# 5_8GHzRadar.net
KiCad netlist of a schematic drawn in EAGLE
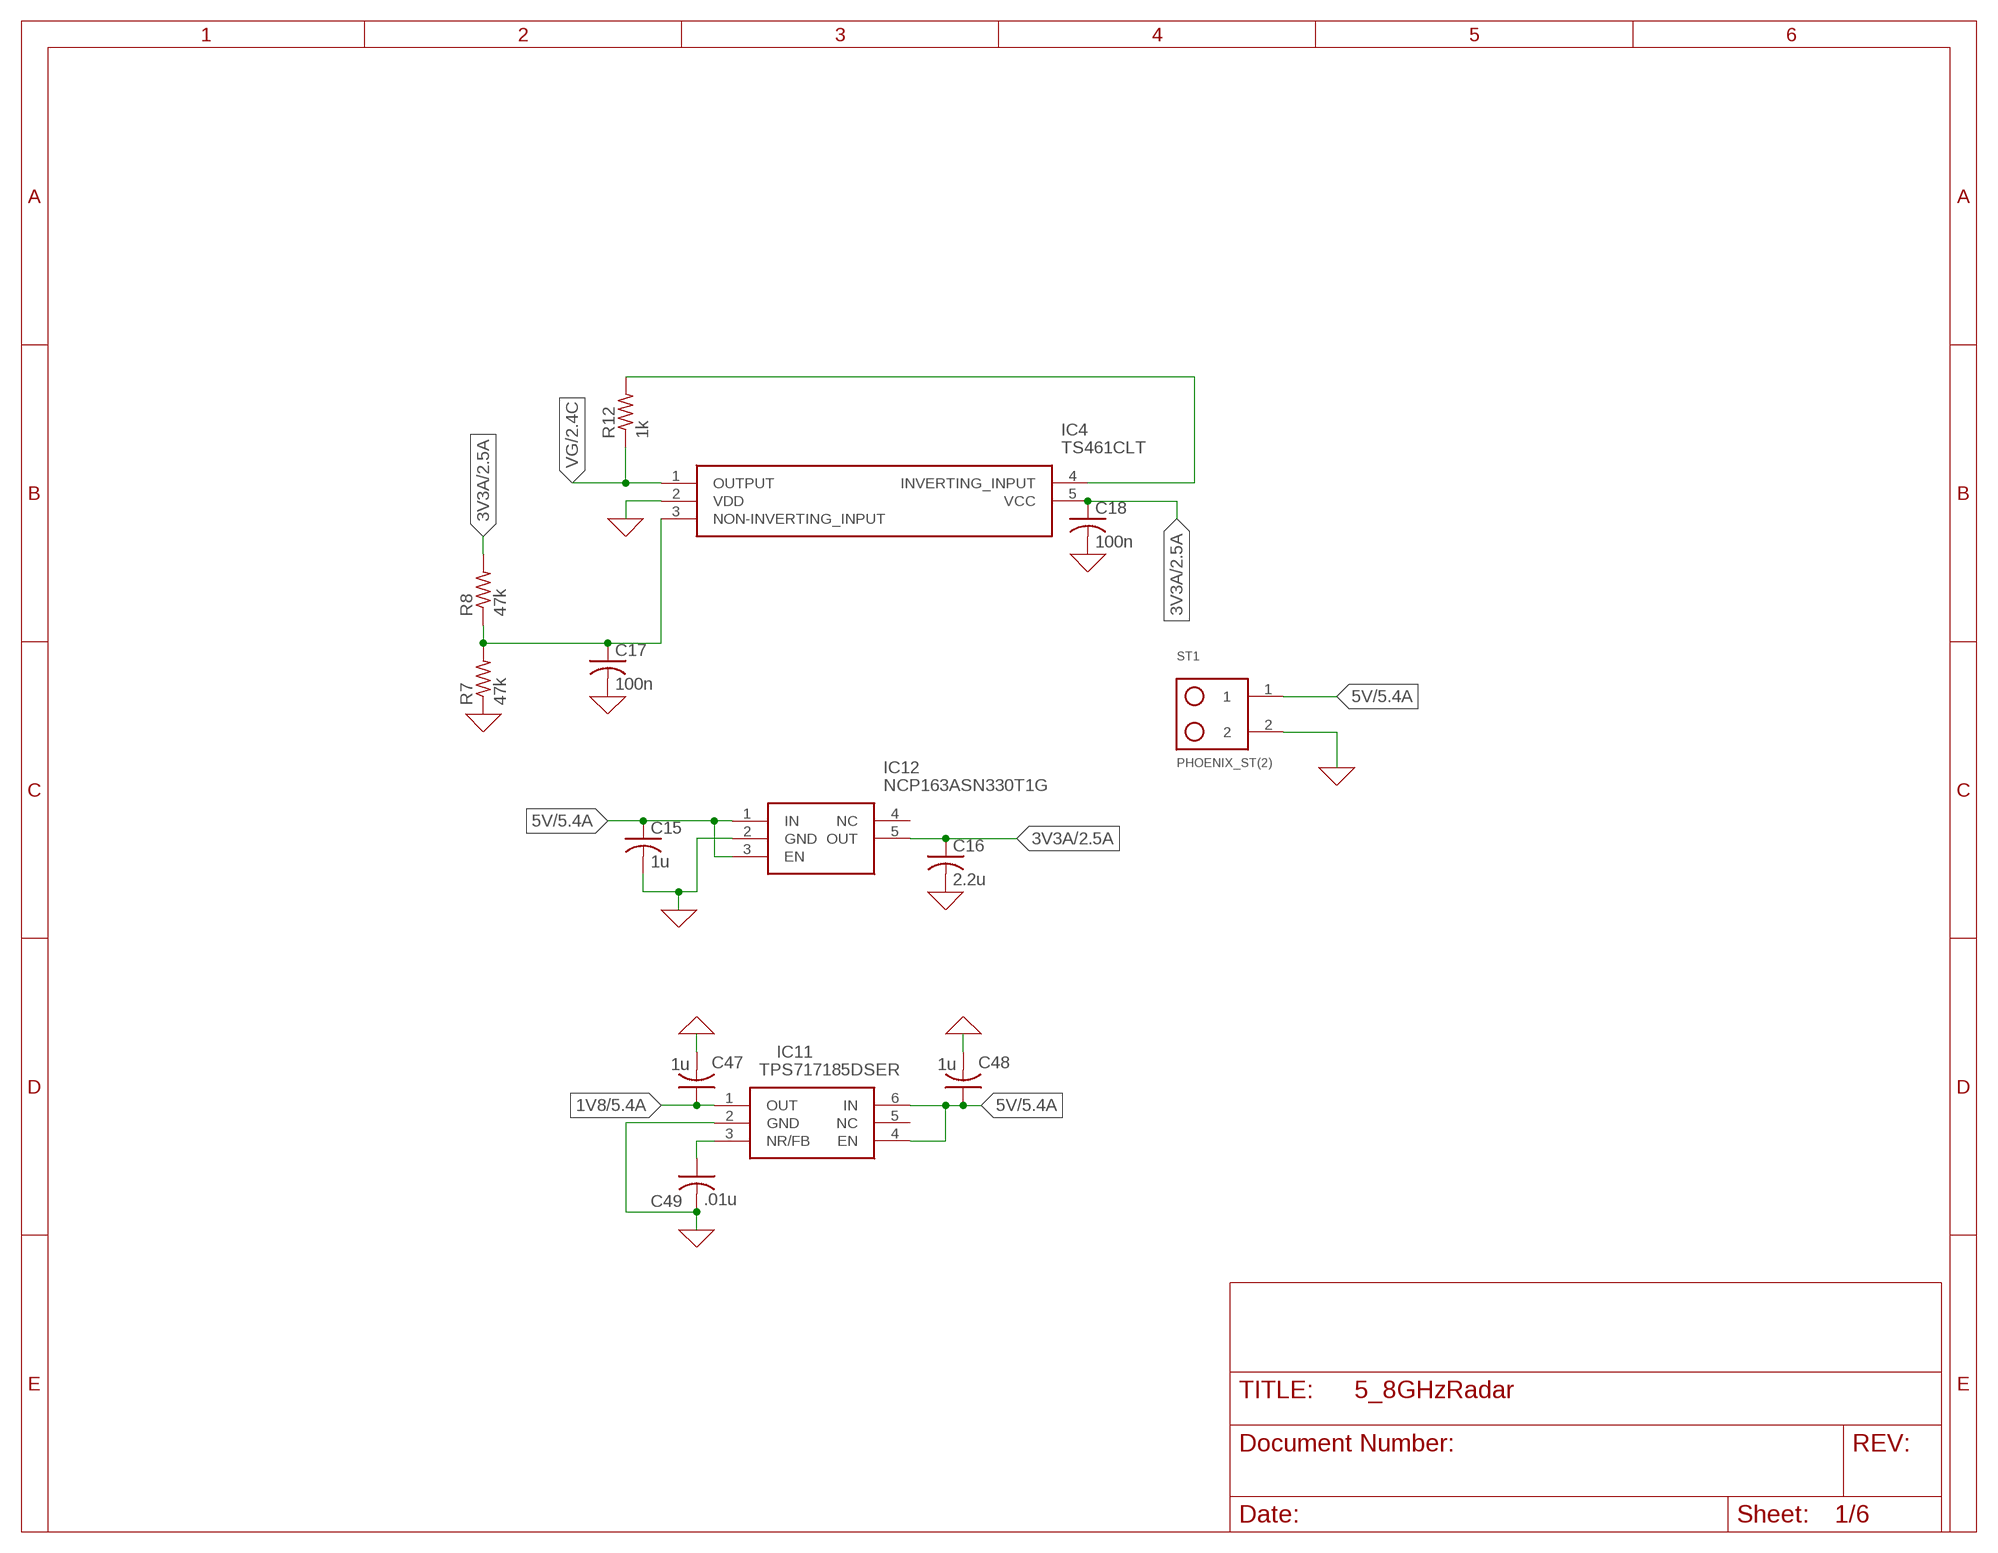
[diagram p0: schematic, sheet 1]
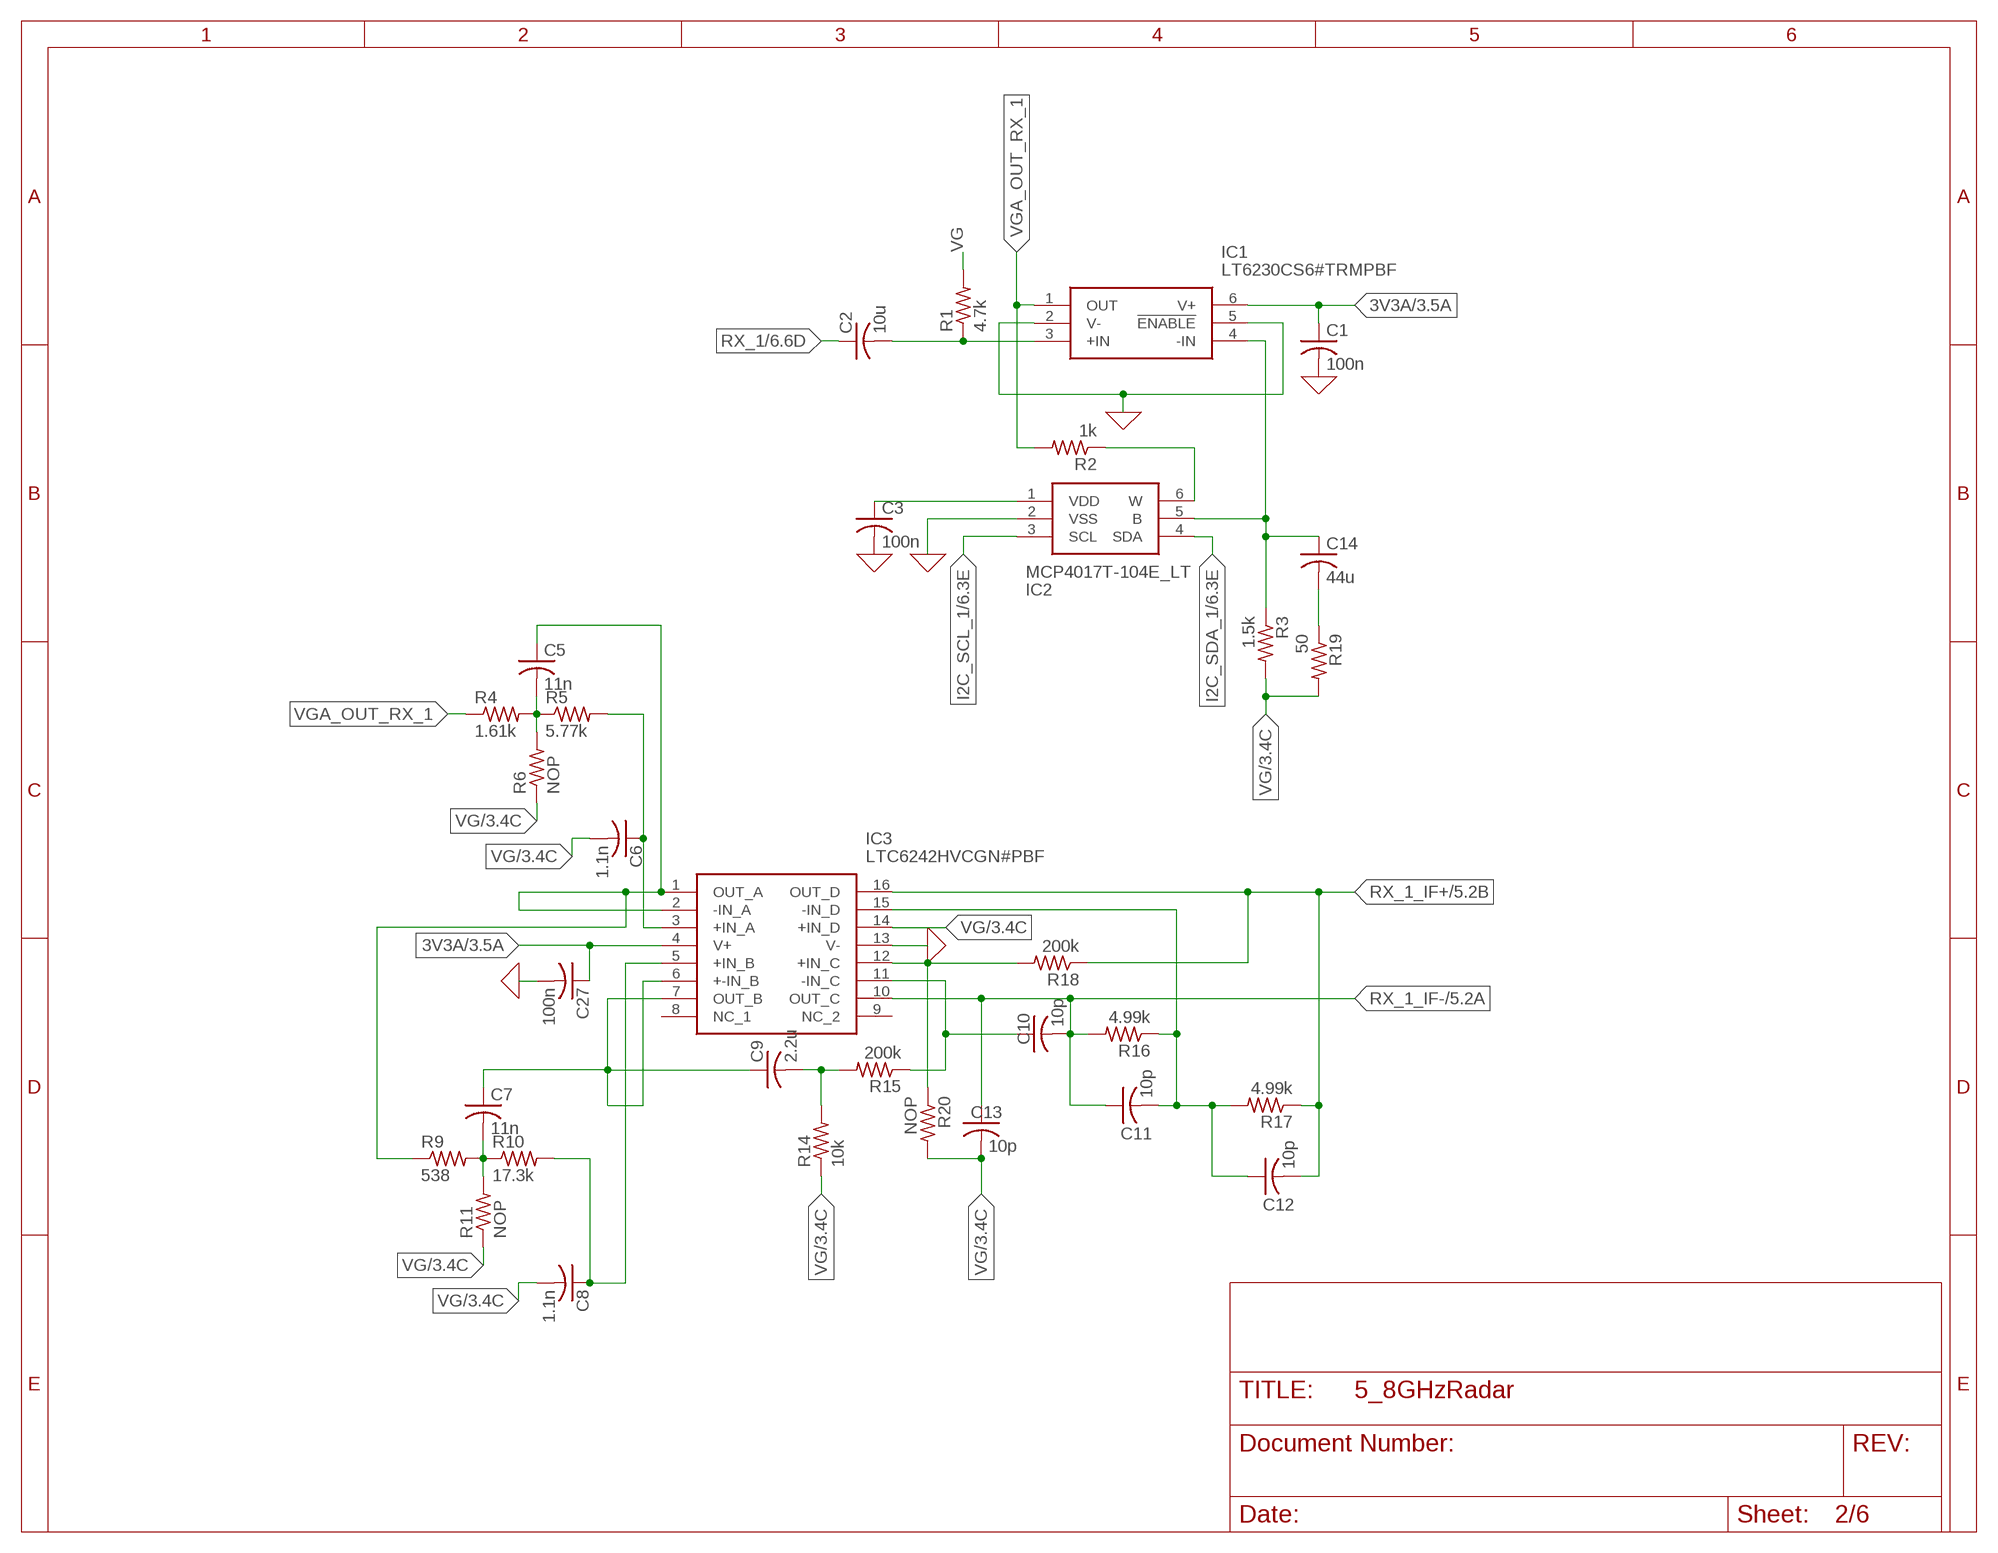
[diagram p1: schematic, sheet 2]
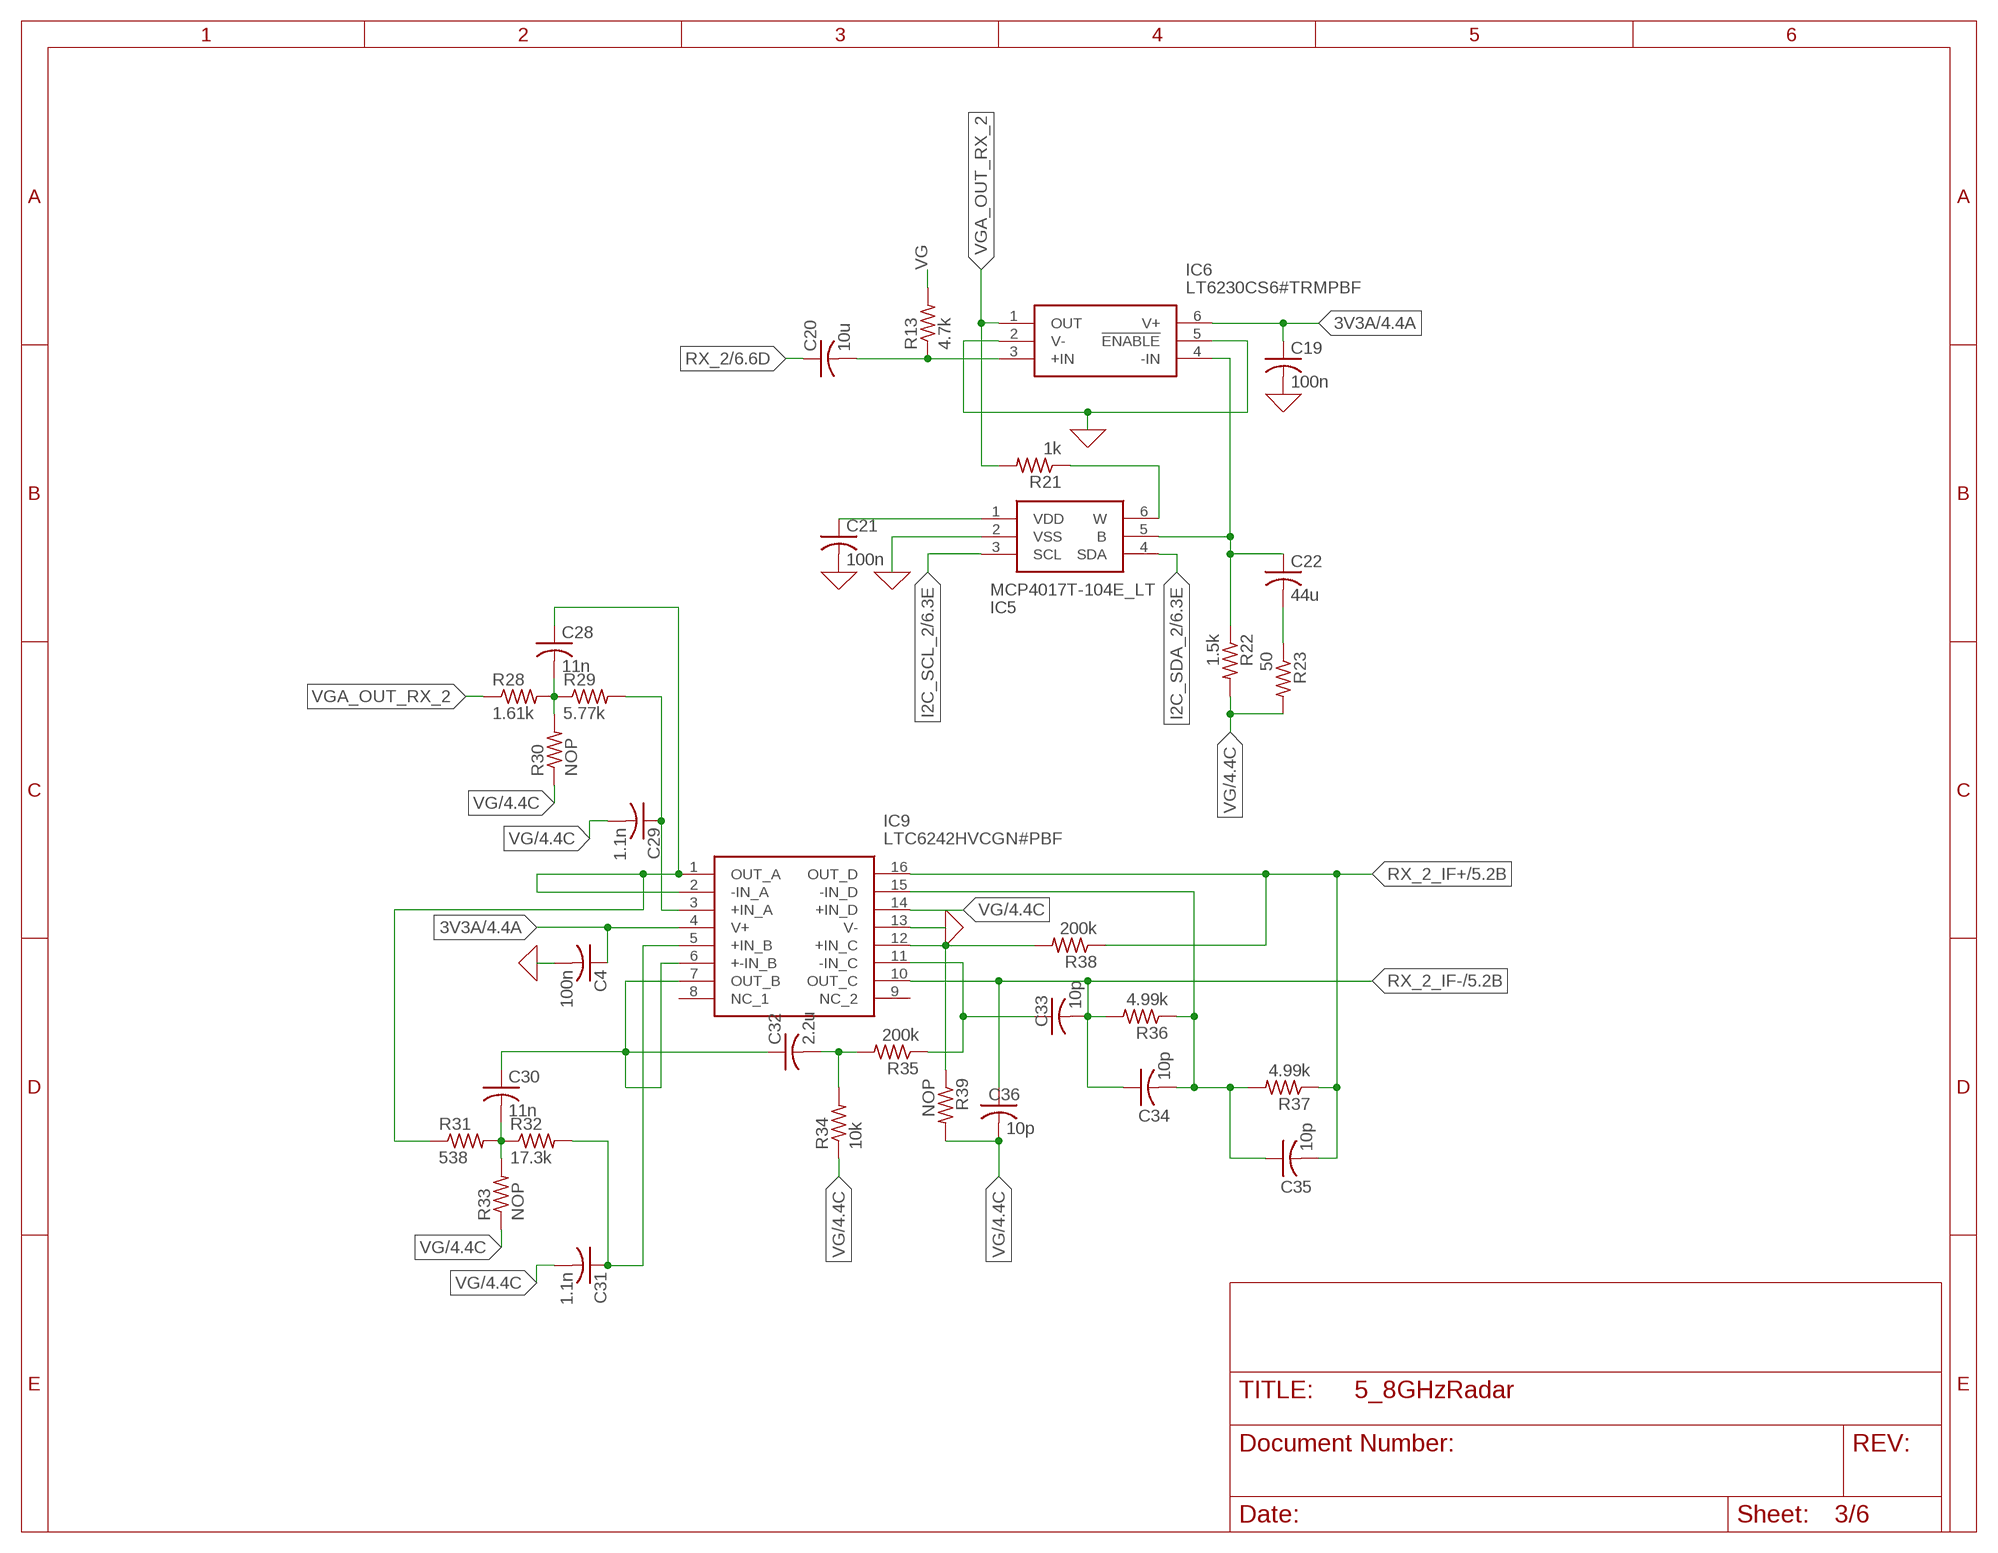
[diagram p2: schematic, sheet 3]
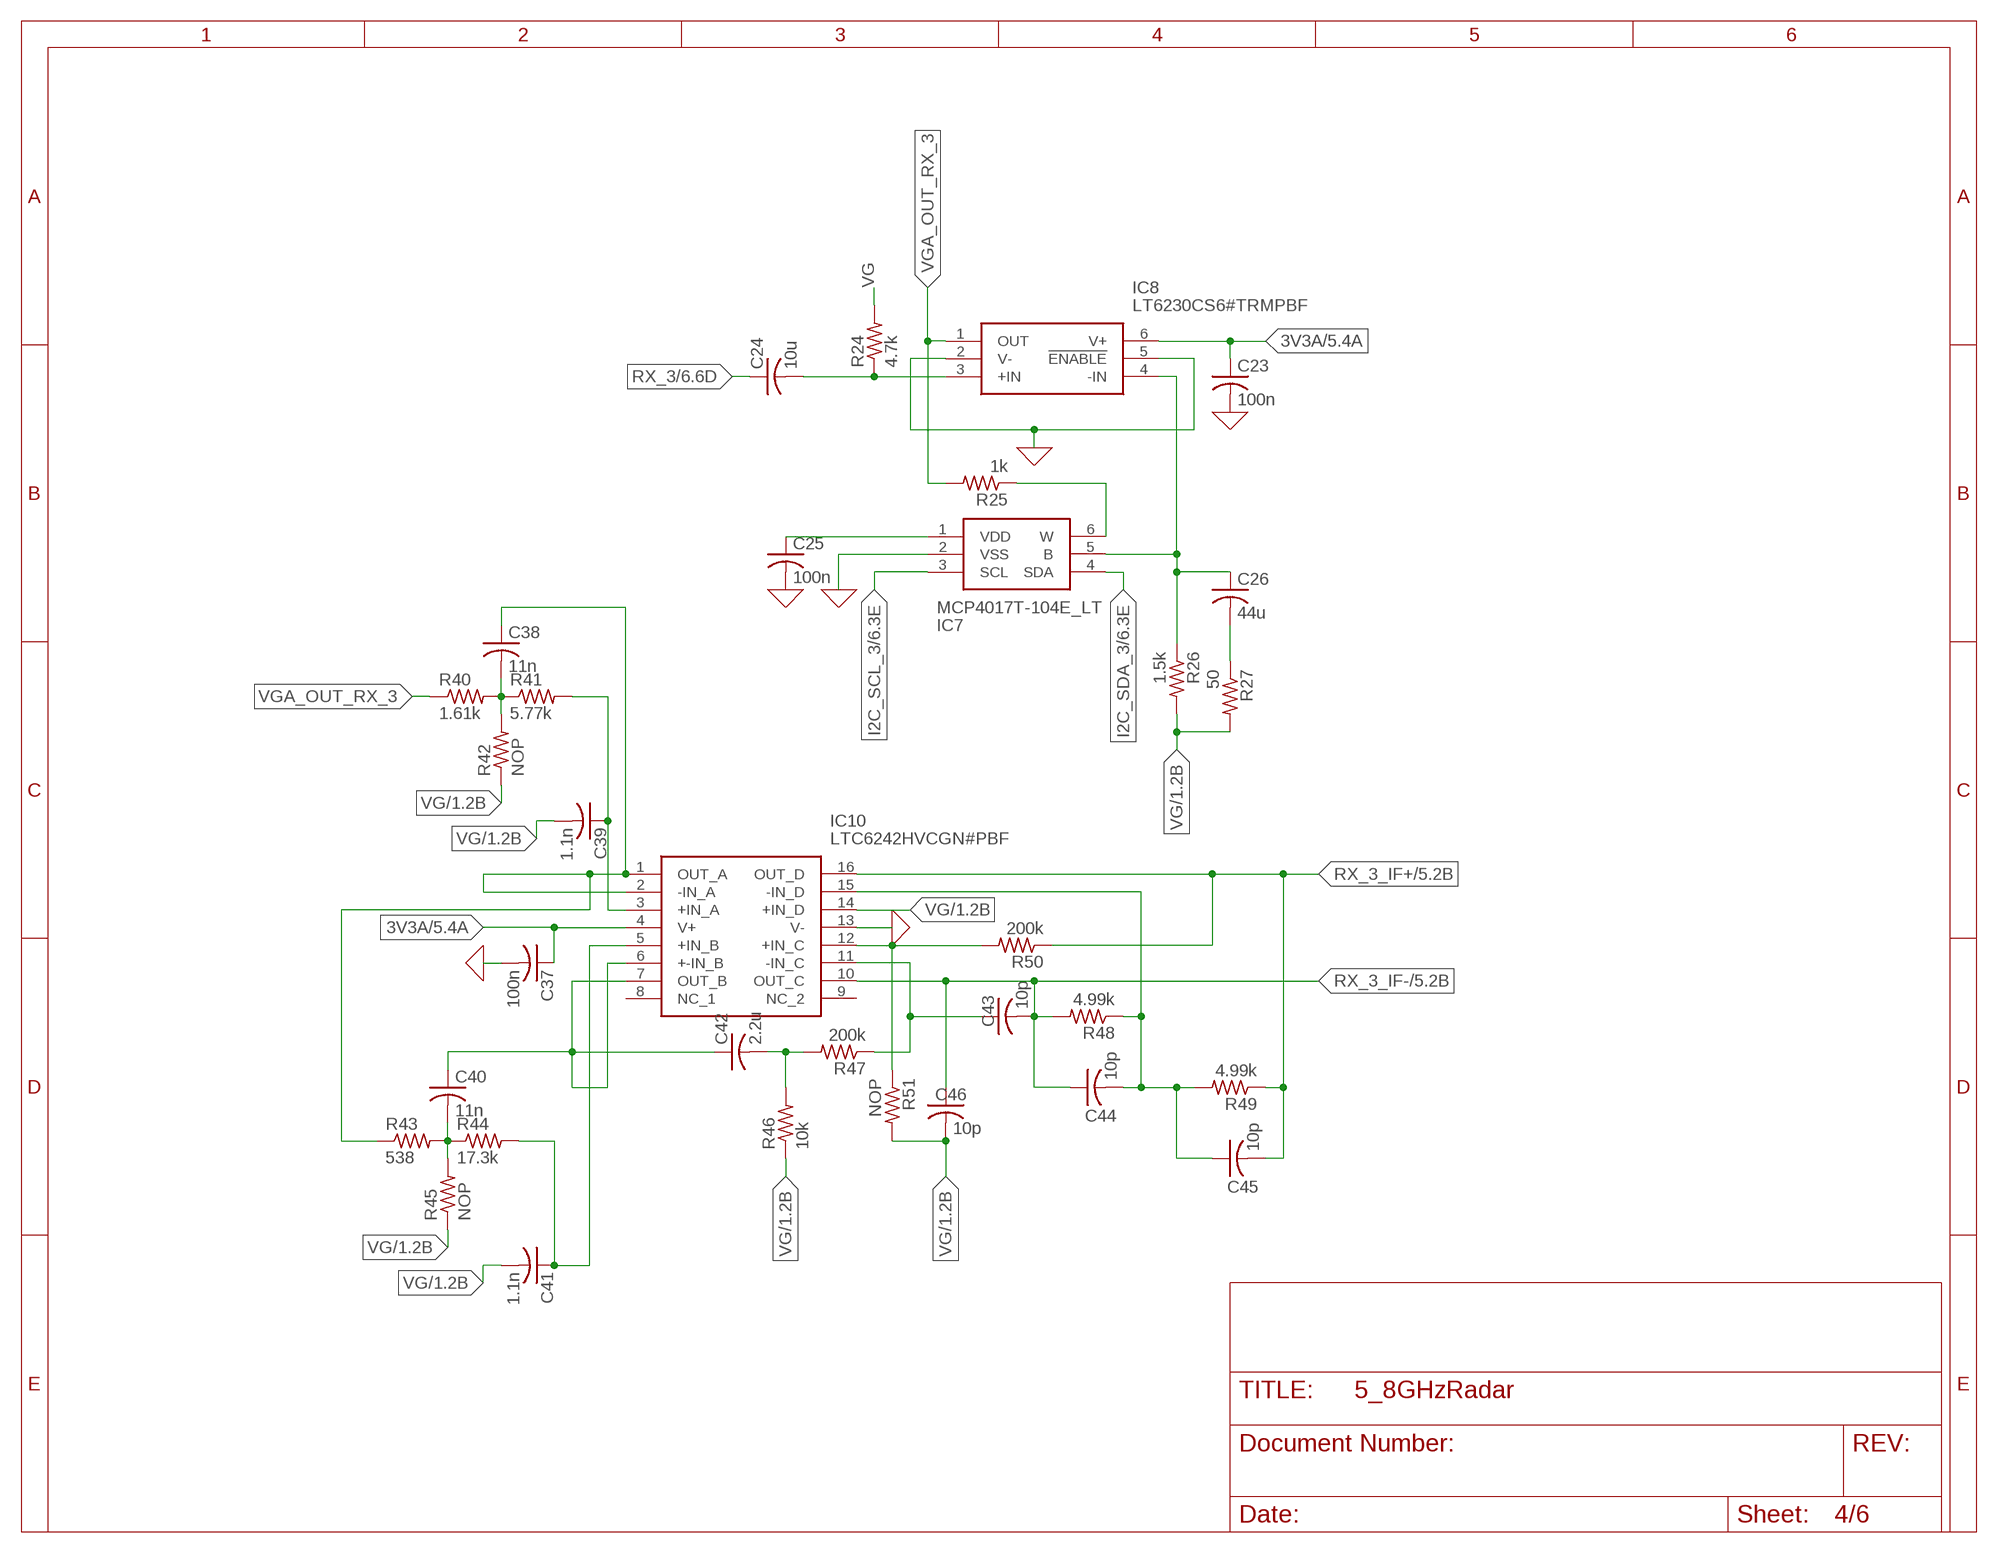
[diagram p3: schematic, sheet 4]
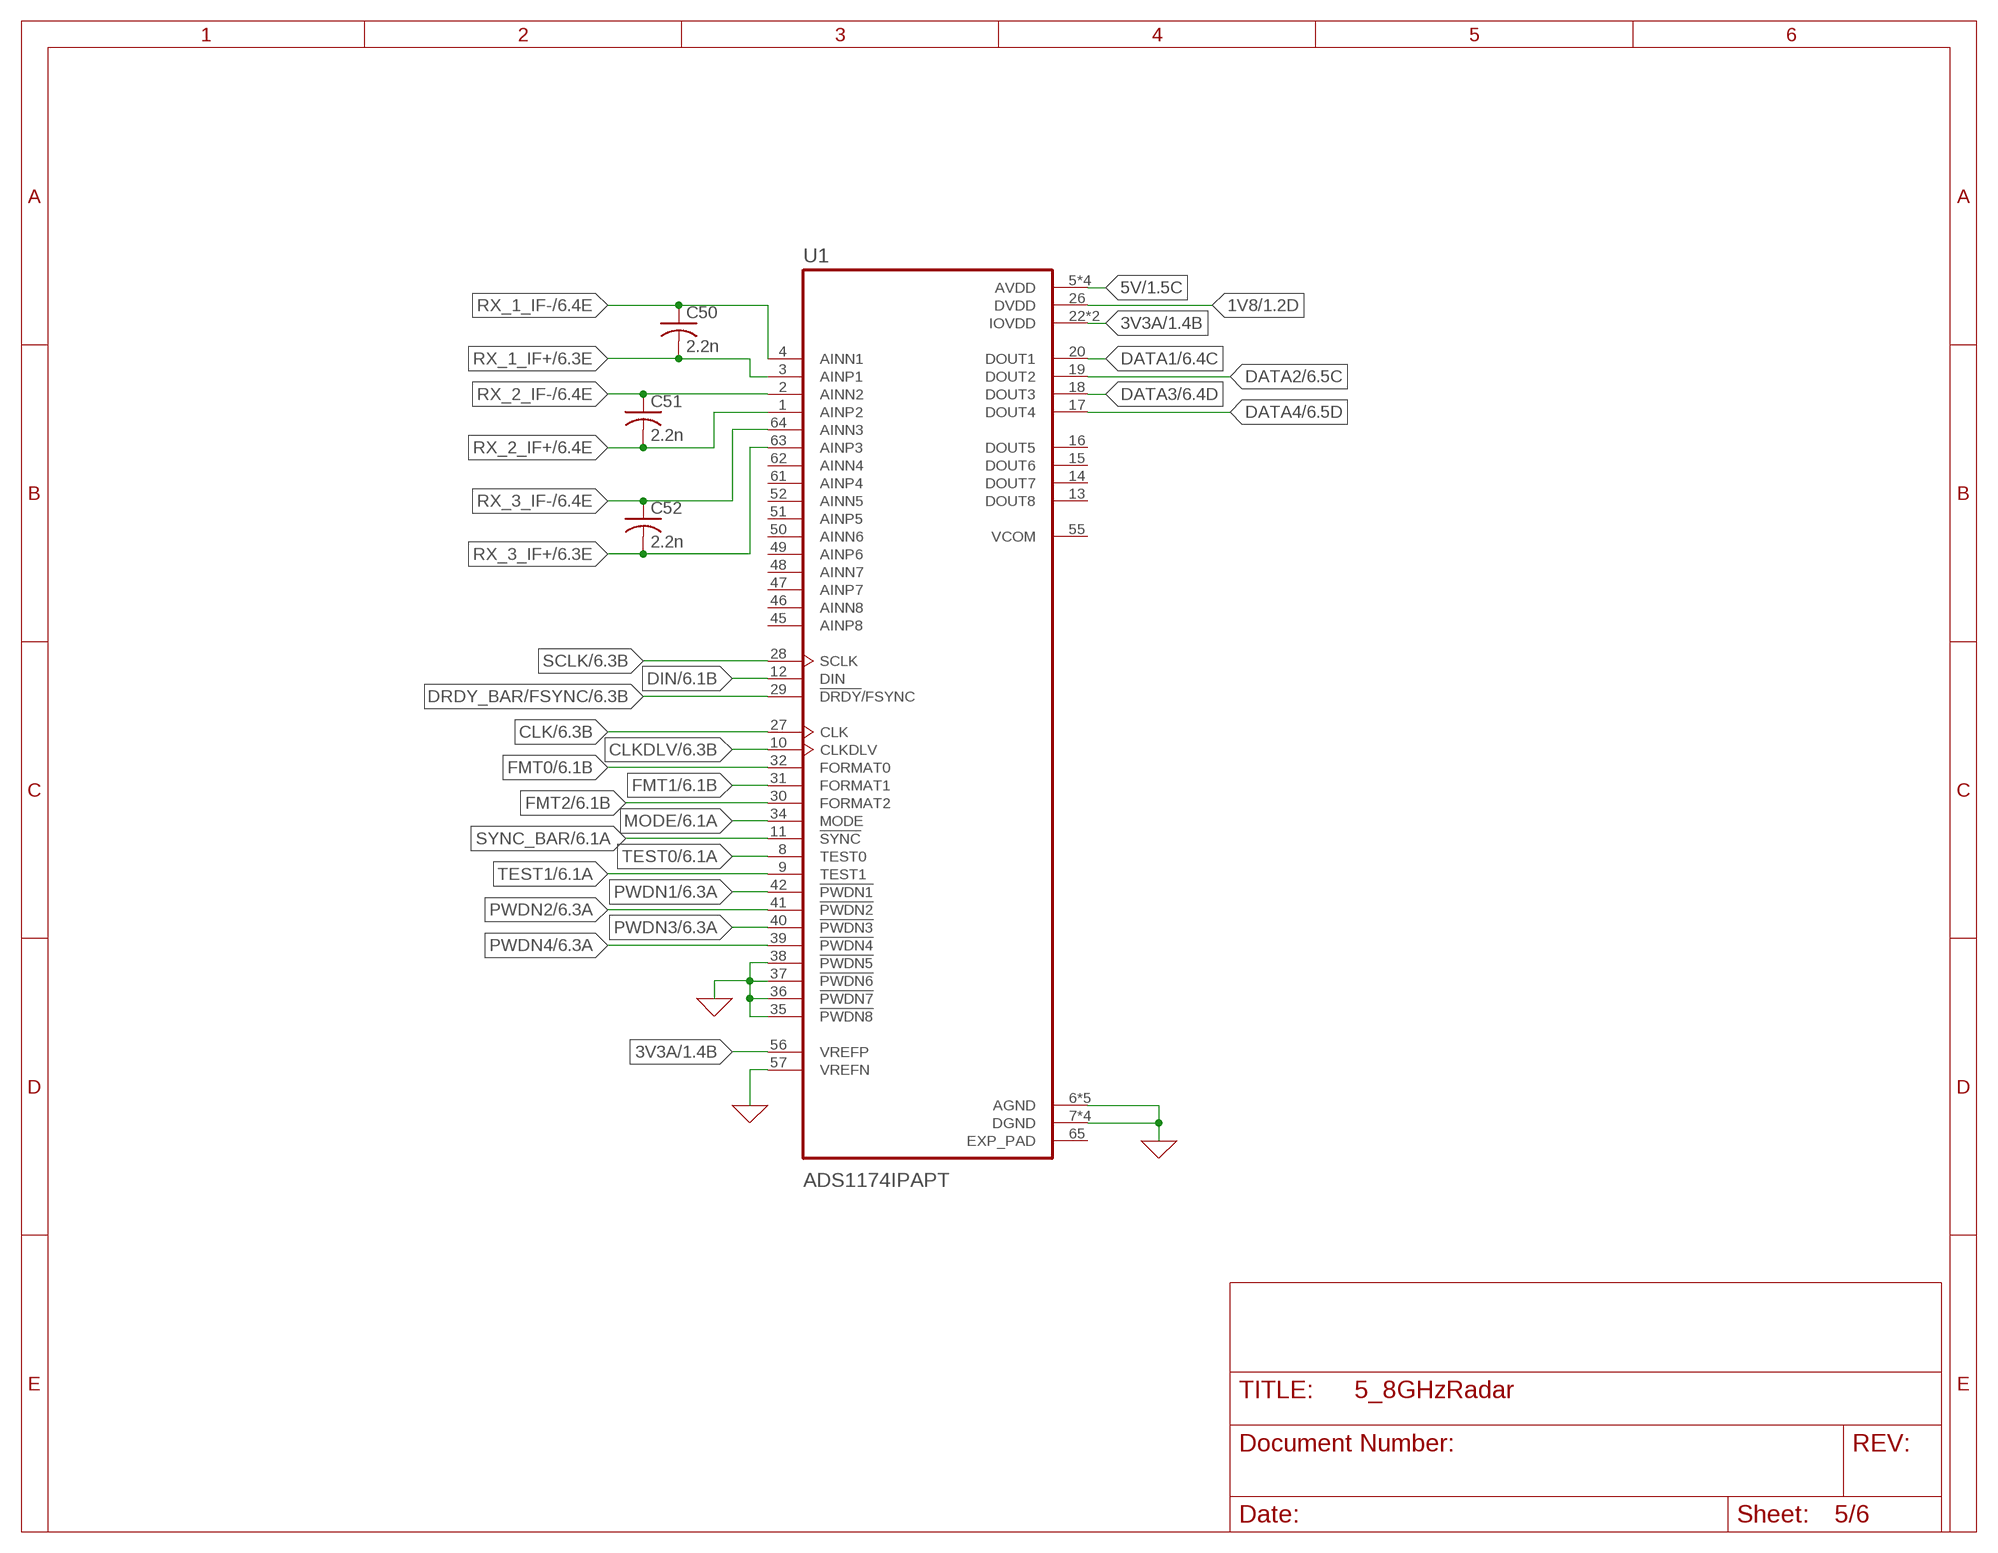
[diagram p4: schematic, sheet 5]
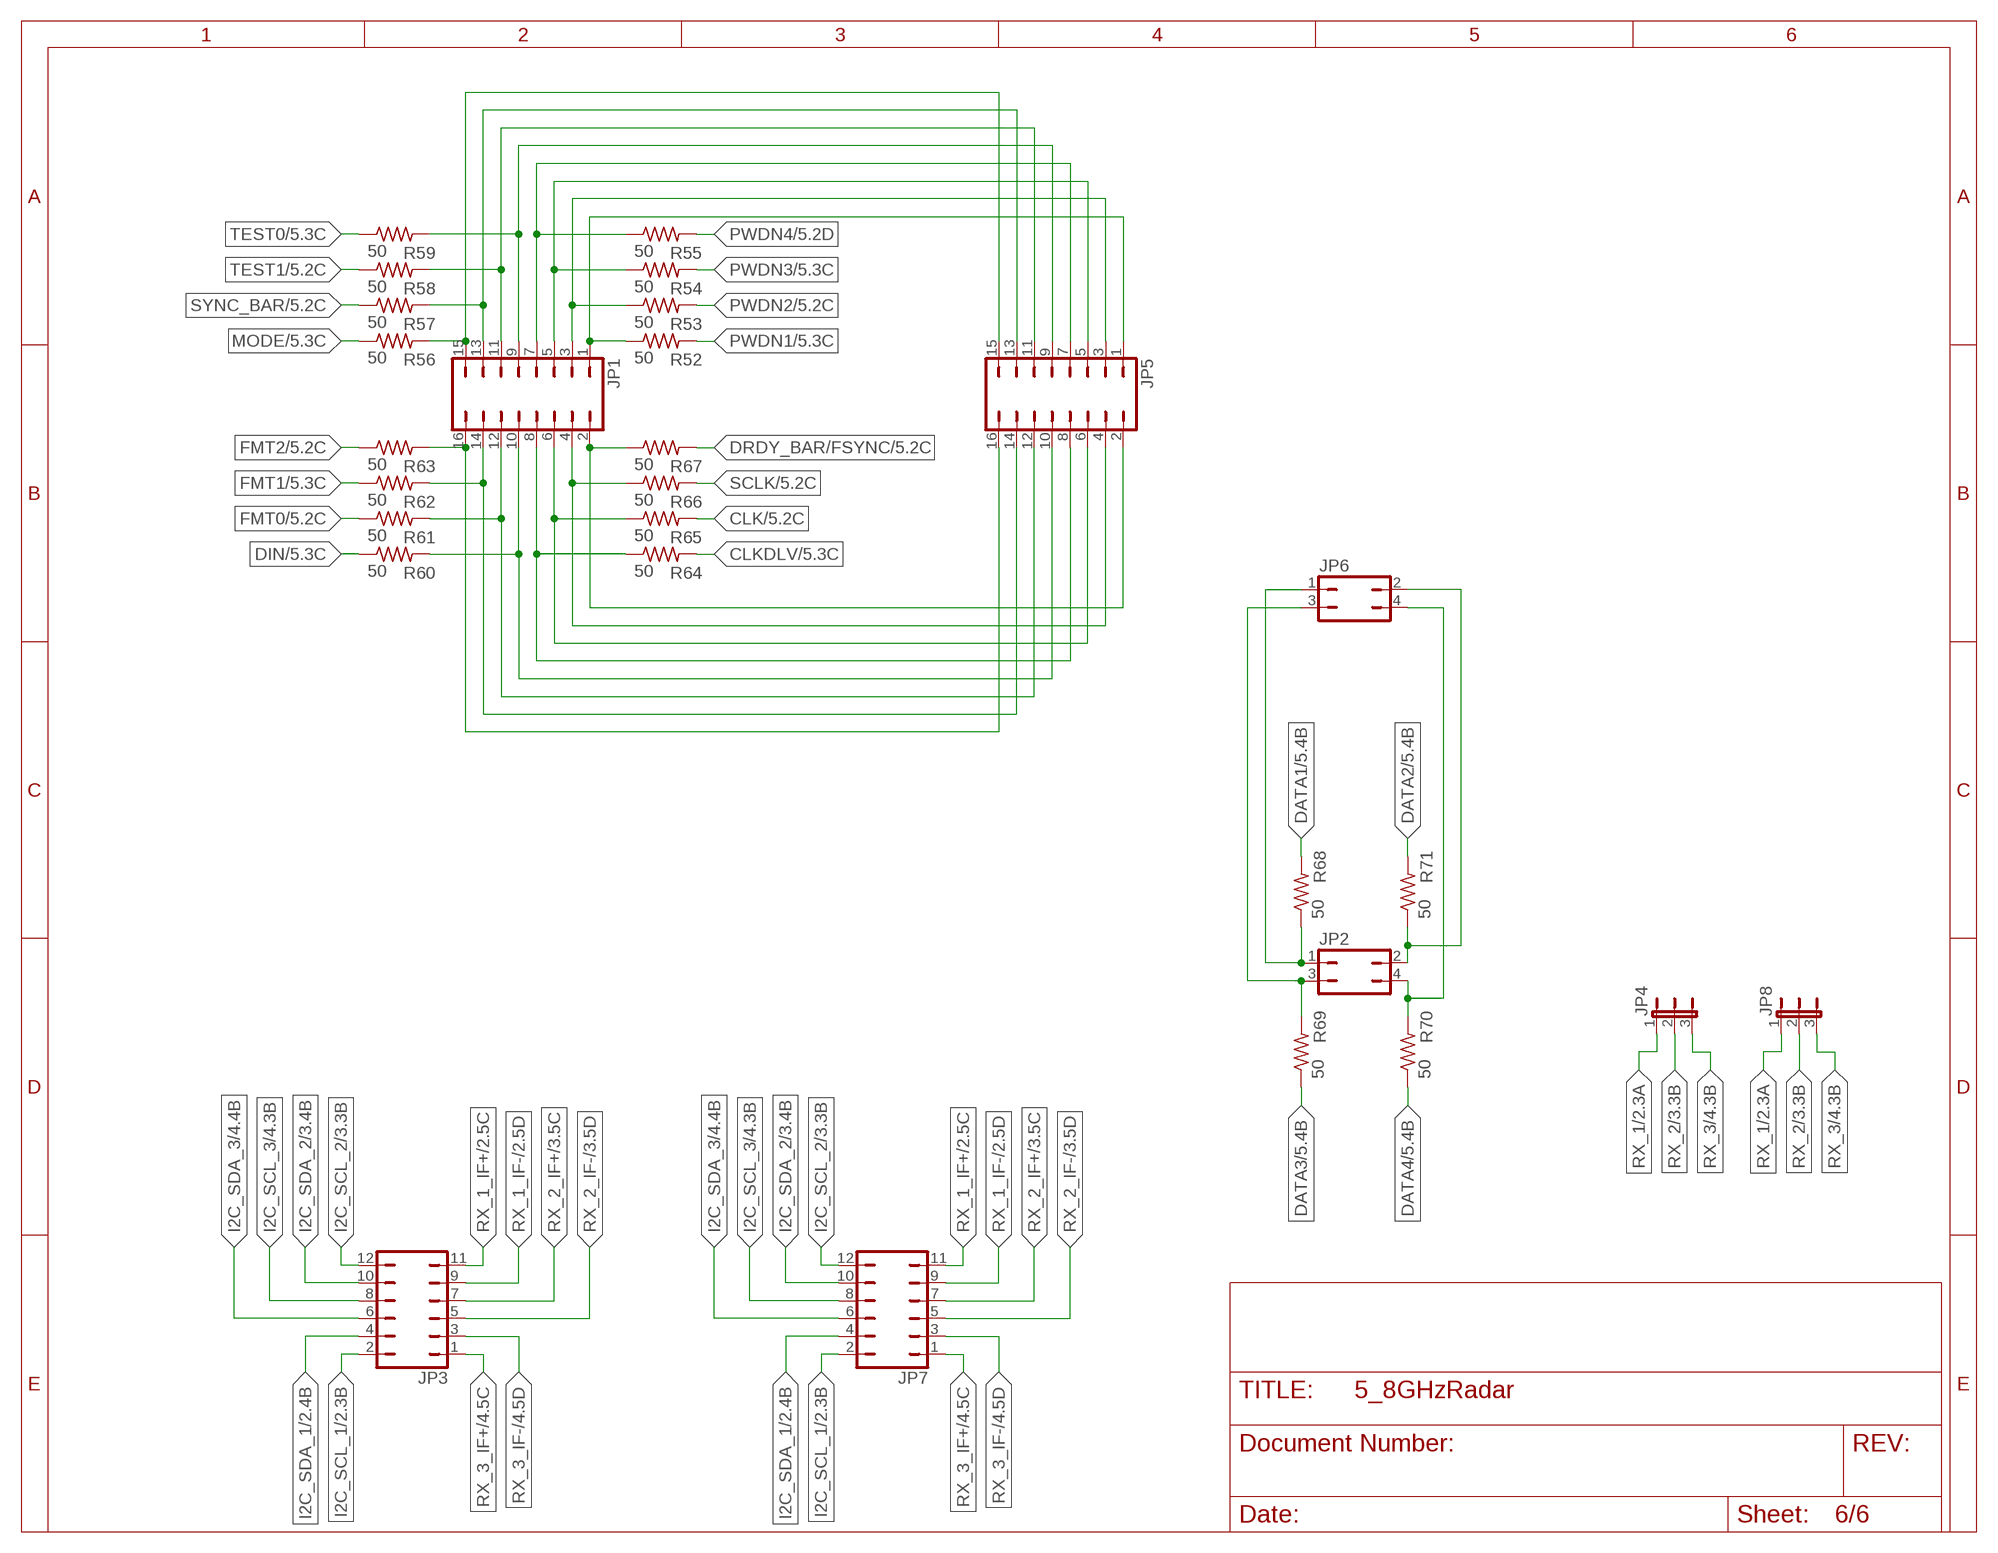
[diagram p5: schematic, sheet 6]

(export (version "E")
  (design (tool "Eeschema 10.0.6"))
  (components
    (comp (ref "C15")
      (value "1u")
      (footprint "eagle-import:C0805")
      (libsource (lib "eagle-import") (part "C-USC0805"))
    )
    (comp (ref "C16")
      (value "2.2u")
      (footprint "eagle-import:C0805")
      (libsource (lib "eagle-import") (part "C-USC0805"))
    )
    (comp (ref "C17")
      (value "100n")
      (footprint "eagle-import:C0805")
      (libsource (lib "eagle-import") (part "C-USC0805"))
    )
    (comp (ref "C18")
      (value "100n")
      (footprint "eagle-import:C0805")
      (libsource (lib "eagle-import") (part "C-USC0805"))
    )
    (comp (ref "C47")
      (value "1u")
      (footprint "eagle-import:C0805")
      (libsource (lib "eagle-import") (part "C-USC0805"))
    )
    (comp (ref "C48")
      (value "1u")
      (footprint "eagle-import:C0805")
      (libsource (lib "eagle-import") (part "C-USC0805"))
    )
    (comp (ref "C49")
      (value ".01u")
      (footprint "eagle-import:C0805")
      (libsource (lib "eagle-import") (part "C-USC0805"))
    )
    (comp (ref "IC4")
      (value "TS461CLT")
      (footprint "eagle-import:SOT95P280X145-5N@1")
      (fields (field (name "MOUSER_PART_NUMBER") "511-TS461CL") (field (name "RS_PART_NUMBER") "7958505P"))
      (libsource (lib "eagle-import") (part "TS461CLT"))
    )
    (comp (ref "IC11")
      (value "TPS717185DSER")
      (footprint "eagle-import:SON50P150X150X80-6N")
      (fields (field (name "MOUSER_PART_NUMBER") "595-TPS717185DSER"))
      (libsource (lib "eagle-import") (part "TPS717185DSER"))
    )
    (comp (ref "IC12")
      (value "NCP163ASN330T1G")
      (footprint "eagle-import:SOT95P280X145-5N")
      (fields
        (field (name "MOUSER_PART_NUMBER") "863-NCP163ASN330T1G")
        (field (name "RS_PART_NUMBER") "1890394")
      )
      (libsource (lib "eagle-import") (part "NCP163ASN330T1G"))
    )
    (comp (ref "R7")
      (value "47k")
      (footprint "eagle-import:R0805")
      (libsource (lib "eagle-import") (part "R-US_R0805"))
    )
    (comp (ref "R8")
      (value "47k")
      (footprint "eagle-import:R0805")
      (libsource (lib "eagle-import") (part "R-US_R0805"))
    )
    (comp (ref "R12")
      (value "1k")
      (footprint "eagle-import:R0805")
      (libsource (lib "eagle-import") (part "R-US_R0805"))
    )
    (comp (ref "ST1")
      (value "PHOENIX_ST(2)")
      (footprint "eagle-import:PHEONIX_SCREW(2)")
      (libsource (lib "eagle-import") (part "PHOENIX_ST(2)"))
    )
    (comp (ref "C23")
      (value "100n")
      (footprint "eagle-import:C0805")
      (libsource (lib "eagle-import") (part "C-USC0805"))
    )
    (comp (ref "C24")
      (value "10u")
      (footprint "eagle-import:C0805")
      (libsource (lib "eagle-import") (part "C-USC0805"))
    )
    (comp (ref "C25")
      (value "100n")
      (footprint "eagle-import:C0805")
      (libsource (lib "eagle-import") (part "C-USC0805"))
    )
    (comp (ref "C26")
      (value "44u")
      (footprint "eagle-import:C0805")
      (libsource (lib "eagle-import") (part "C-USC0805"))
    )
    (comp (ref "C37")
      (value "100n")
      (footprint "eagle-import:C0805")
      (libsource (lib "eagle-import") (part "C-USC0805"))
    )
    (comp (ref "C38")
      (value "11n")
      (footprint "eagle-import:C0805")
      (libsource (lib "eagle-import") (part "C-USC0805"))
    )
    (comp (ref "C39")
      (value "1.1n")
      (footprint "eagle-import:C0805")
      (libsource (lib "eagle-import") (part "C-USC0805"))
    )
    (comp (ref "C40")
      (value "11n")
      (footprint "eagle-import:C0805")
      (libsource (lib "eagle-import") (part "C-USC0805"))
    )
    (comp (ref "C41")
      (value "1.1n")
      (footprint "eagle-import:C0805")
      (libsource (lib "eagle-import") (part "C-USC0805"))
    )
    (comp (ref "C42")
      (value "2.2u")
      (footprint "eagle-import:C0805")
      (libsource (lib "eagle-import") (part "C-USC0805"))
    )
    (comp (ref "C43")
      (value "10p")
      (footprint "eagle-import:C0805")
      (libsource (lib "eagle-import") (part "C-USC0805"))
    )
    (comp (ref "C44")
      (value "10p")
      (footprint "eagle-import:C0805")
      (libsource (lib "eagle-import") (part "C-USC0805"))
    )
    (comp (ref "C45")
      (value "10p")
      (footprint "eagle-import:C0805")
      (libsource (lib "eagle-import") (part "C-USC0805"))
    )
    (comp (ref "C46")
      (value "10p")
      (footprint "eagle-import:C0805")
      (libsource (lib "eagle-import") (part "C-USC0805"))
    )
    (comp (ref "IC7")
      (value "MCP4017T-104E_LT")
      (footprint "eagle-import:SOT65P210X110-6N")
      (fields
        (field (name "MANUFACTURER_PART_NUMBER") "MCP4017T-104E/LT")
        (field (name "MOUSER_PART_NUMBER") "579-MCP4017T104E/LT")
        (field (name "RS_PART_NUMBER") "7386799P")
      )
      (libsource (lib "eagle-import") (part "MCP4017T-104E_LT"))
    )
    (comp (ref "IC8")
      (value "LT6230CS6#TRMPBF")
      (footprint "eagle-import:SOT95P280X100-6N")
      (fields
        (field (name "MOUSER_PART_NUMBER") "584-LT6230CS6#TRMPBF")
        (field (name "RS_PART_NUMBER") "5061202P")
      )
      (libsource (lib "eagle-import") (part "LT6230CS6#TRMPBF"))
    )
    (comp (ref "IC10")
      (value "LTC6242HVCGN#PBF")
      (footprint "eagle-import:SOP64P601X175-16N")
      (fields (field (name "MOUSER_PART_NUMBER") "584-LTC6242HVCGN#PBF"))
      (libsource (lib "eagle-import") (part "LTC6242HVCGN#PBF"))
    )
    (comp (ref "R24")
      (value "4.7k")
      (footprint "eagle-import:R0805")
      (libsource (lib "eagle-import") (part "R-US_R0805"))
    )
    (comp (ref "R25")
      (value "1k")
      (footprint "eagle-import:R0805")
      (libsource (lib "eagle-import") (part "R-US_R0805"))
    )
    (comp (ref "R26")
      (value "1.5k")
      (footprint "eagle-import:R0805")
      (libsource (lib "eagle-import") (part "R-US_R0805"))
    )
    (comp (ref "R27")
      (value "50")
      (footprint "eagle-import:R0805")
      (libsource (lib "eagle-import") (part "R-US_R0805"))
    )
    (comp (ref "R40")
      (value "1.61k")
      (footprint "eagle-import:R0805")
      (libsource (lib "eagle-import") (part "R-US_R0805"))
    )
    (comp (ref "R41")
      (value "5.77k")
      (footprint "eagle-import:R0805")
      (libsource (lib "eagle-import") (part "R-US_R0805"))
    )
    (comp (ref "R42")
      (value "NOP")
      (footprint "eagle-import:R0805")
      (libsource (lib "eagle-import") (part "R-US_R0805"))
    )
    (comp (ref "R43")
      (value "538")
      (footprint "eagle-import:R0805")
      (libsource (lib "eagle-import") (part "R-US_R0805"))
    )
    (comp (ref "R44")
      (value "17.3k")
      (footprint "eagle-import:R0805")
      (libsource (lib "eagle-import") (part "R-US_R0805"))
    )
    (comp (ref "R45")
      (value "NOP")
      (footprint "eagle-import:R0805")
      (libsource (lib "eagle-import") (part "R-US_R0805"))
    )
    (comp (ref "R46")
      (value "10k")
      (footprint "eagle-import:R0805")
      (libsource (lib "eagle-import") (part "R-US_R0805"))
    )
    (comp (ref "R47")
      (value "200k")
      (footprint "eagle-import:R0805")
      (libsource (lib "eagle-import") (part "R-US_R0805"))
    )
    (comp (ref "R48")
      (value "4.99k")
      (footprint "eagle-import:R0805")
      (libsource (lib "eagle-import") (part "R-US_R0805"))
    )
    (comp (ref "R49")
      (value "4.99k")
      (footprint "eagle-import:R0805")
      (libsource (lib "eagle-import") (part "R-US_R0805"))
    )
    (comp (ref "R50")
      (value "200k")
      (footprint "eagle-import:R0805")
      (libsource (lib "eagle-import") (part "R-US_R0805"))
    )
    (comp (ref "R51")
      (value "NOP")
      (footprint "eagle-import:R0805")
      (libsource (lib "eagle-import") (part "R-US_R0805"))
    )
    (comp (ref "JP1")
      (value "JP8Q")
      (footprint "eagle-import:JP8Q")
      (libsource (lib "eagle-import") (part "JP8Q"))
    )
    (comp (ref "JP2")
      (value "JP2Q")
      (footprint "eagle-import:JP2Q")
      (libsource (lib "eagle-import") (part "JP2Q"))
    )
    (comp (ref "JP3")
      (value "JP6Q")
      (footprint "eagle-import:JP6Q")
      (libsource (lib "eagle-import") (part "JP6Q"))
    )
    (comp (ref "JP4")
      (value "JP2E")
      (footprint "eagle-import:JP2")
      (libsource (lib "eagle-import") (part "JP2E"))
    )
    (comp (ref "JP5")
      (value "JP8Q")
      (footprint "eagle-import:JP8Q")
      (libsource (lib "eagle-import") (part "JP8Q"))
    )
    (comp (ref "JP6")
      (value "JP2Q")
      (footprint "eagle-import:JP2Q")
      (libsource (lib "eagle-import") (part "JP2Q"))
    )
    (comp (ref "JP7")
      (value "JP6Q")
      (footprint "eagle-import:JP6Q")
      (libsource (lib "eagle-import") (part "JP6Q"))
    )
    (comp (ref "JP8")
      (value "JP2E")
      (footprint "eagle-import:JP2")
      (libsource (lib "eagle-import") (part "JP2E"))
    )
    (comp (ref "R52")
      (value "50")
      (footprint "eagle-import:R0805")
      (libsource (lib "eagle-import") (part "R-US_R0805"))
    )
    (comp (ref "R53")
      (value "50")
      (footprint "eagle-import:R0805")
      (libsource (lib "eagle-import") (part "R-US_R0805"))
    )
    (comp (ref "R54")
      (value "50")
      (footprint "eagle-import:R0805")
      (libsource (lib "eagle-import") (part "R-US_R0805"))
    )
    (comp (ref "R55")
      (value "50")
      (footprint "eagle-import:R0805")
      (libsource (lib "eagle-import") (part "R-US_R0805"))
    )
    (comp (ref "R56")
      (value "50")
      (footprint "eagle-import:R0805")
      (libsource (lib "eagle-import") (part "R-US_R0805"))
    )
    (comp (ref "R57")
      (value "50")
      (footprint "eagle-import:R0805")
      (libsource (lib "eagle-import") (part "R-US_R0805"))
    )
    (comp (ref "R58")
      (value "50")
      (footprint "eagle-import:R0805")
      (libsource (lib "eagle-import") (part "R-US_R0805"))
    )
    (comp (ref "R59")
      (value "50")
      (footprint "eagle-import:R0805")
      (libsource (lib "eagle-import") (part "R-US_R0805"))
    )
    (comp (ref "R60")
      (value "50")
      (footprint "eagle-import:R0805")
      (libsource (lib "eagle-import") (part "R-US_R0805"))
    )
    (comp (ref "R61")
      (value "50")
      (footprint "eagle-import:R0805")
      (libsource (lib "eagle-import") (part "R-US_R0805"))
    )
    (comp (ref "R62")
      (value "50")
      (footprint "eagle-import:R0805")
      (libsource (lib "eagle-import") (part "R-US_R0805"))
    )
    (comp (ref "R63")
      (value "50")
      (footprint "eagle-import:R0805")
      (libsource (lib "eagle-import") (part "R-US_R0805"))
    )
    (comp (ref "R64")
      (value "50")
      (footprint "eagle-import:R0805")
      (libsource (lib "eagle-import") (part "R-US_R0805"))
    )
    (comp (ref "R65")
      (value "50")
      (footprint "eagle-import:R0805")
      (libsource (lib "eagle-import") (part "R-US_R0805"))
    )
    (comp (ref "R66")
      (value "50")
      (footprint "eagle-import:R0805")
      (libsource (lib "eagle-import") (part "R-US_R0805"))
    )
    (comp (ref "R67")
      (value "50")
      (footprint "eagle-import:R0805")
      (libsource (lib "eagle-import") (part "R-US_R0805"))
    )
    (comp (ref "R68")
      (value "50")
      (footprint "eagle-import:R0805")
      (libsource (lib "eagle-import") (part "R-US_R0805"))
    )
    (comp (ref "R69")
      (value "50")
      (footprint "eagle-import:R0805")
      (libsource (lib "eagle-import") (part "R-US_R0805"))
    )
    (comp (ref "R70")
      (value "50")
      (footprint "eagle-import:R0805")
      (libsource (lib "eagle-import") (part "R-US_R0805"))
    )
    (comp (ref "R71")
      (value "50")
      (footprint "eagle-import:R0805")
      (libsource (lib "eagle-import") (part "R-US_R0805"))
    )
    (comp (ref "C1")
      (value "100n")
      (footprint "eagle-import:C0805")
      (libsource (lib "eagle-import") (part "C-USC0805"))
    )
    (comp (ref "C2")
      (value "10u")
      (footprint "eagle-import:C0805")
      (libsource (lib "eagle-import") (part "C-USC0805"))
    )
    (comp (ref "C3")
      (value "100n")
      (footprint "eagle-import:C0805")
      (libsource (lib "eagle-import") (part "C-USC0805"))
    )
    (comp (ref "C5")
      (value "11n")
      (footprint "eagle-import:C0805")
      (libsource (lib "eagle-import") (part "C-USC0805"))
    )
    (comp (ref "C6")
      (value "1.1n")
      (footprint "eagle-import:C0805")
      (libsource (lib "eagle-import") (part "C-USC0805"))
    )
    (comp (ref "C7")
      (value "11n")
      (footprint "eagle-import:C0805")
      (libsource (lib "eagle-import") (part "C-USC0805"))
    )
    (comp (ref "C8")
      (value "1.1n")
      (footprint "eagle-import:C0805")
      (libsource (lib "eagle-import") (part "C-USC0805"))
    )
    (comp (ref "C9")
      (value "2.2u")
      (footprint "eagle-import:C0805")
      (libsource (lib "eagle-import") (part "C-USC0805"))
    )
    (comp (ref "C10")
      (value "10p")
      (footprint "eagle-import:C0805")
      (libsource (lib "eagle-import") (part "C-USC0805"))
    )
    (comp (ref "C11")
      (value "10p")
      (footprint "eagle-import:C0805")
      (libsource (lib "eagle-import") (part "C-USC0805"))
    )
    (comp (ref "C12")
      (value "10p")
      (footprint "eagle-import:C0805")
      (libsource (lib "eagle-import") (part "C-USC0805"))
    )
    (comp (ref "C13")
      (value "10p")
      (footprint "eagle-import:C0805")
      (libsource (lib "eagle-import") (part "C-USC0805"))
    )
    (comp (ref "C14")
      (value "44u")
      (footprint "eagle-import:C0603")
      (libsource (lib "eagle-import") (part "C-USC0603"))
    )
    (comp (ref "C27")
      (value "100n")
      (footprint "eagle-import:C0805")
      (libsource (lib "eagle-import") (part "C-USC0805"))
    )
    (comp (ref "IC1")
      (value "LT6230CS6#TRMPBF")
      (footprint "eagle-import:SOT95P280X100-6N")
      (fields
        (field (name "MOUSER_PART_NUMBER") "584-LT6230CS6#TRMPBF")
        (field (name "RS_PART_NUMBER") "5061202P")
      )
      (libsource (lib "eagle-import") (part "LT6230CS6#TRMPBF"))
    )
    (comp (ref "IC2")
      (value "MCP4017T-104E_LT")
      (footprint "eagle-import:SOT65P210X110-6N")
      (fields
        (field (name "MANUFACTURER_PART_NUMBER") "MCP4017T-104E/LT")
        (field (name "MOUSER_PART_NUMBER") "579-MCP4017T104E/LT")
        (field (name "RS_PART_NUMBER") "7386799P")
      )
      (libsource (lib "eagle-import") (part "MCP4017T-104E_LT"))
    )
    (comp (ref "IC3")
      (value "LTC6242HVCGN#PBF")
      (footprint "eagle-import:SOP64P601X175-16N")
      (fields (field (name "MOUSER_PART_NUMBER") "584-LTC6242HVCGN#PBF"))
      (libsource (lib "eagle-import") (part "LTC6242HVCGN#PBF"))
    )
    (comp (ref "R1")
      (value "4.7k")
      (footprint "eagle-import:R0805")
      (libsource (lib "eagle-import") (part "R-US_R0805"))
    )
    (comp (ref "R2")
      (value "1k")
      (footprint "eagle-import:R0805")
      (libsource (lib "eagle-import") (part "R-US_R0805"))
    )
    (comp (ref "R3")
      (value "1.5k")
      (footprint "eagle-import:R0805")
      (libsource (lib "eagle-import") (part "R-US_R0805"))
    )
    (comp (ref "R4")
      (value "1.61k")
      (footprint "eagle-import:R0805")
      (libsource (lib "eagle-import") (part "R-US_R0805"))
    )
    (comp (ref "R5")
      (value "5.77k")
      (footprint "eagle-import:R0805")
      (libsource (lib "eagle-import") (part "R-US_R0805"))
    )
    (comp (ref "R6")
      (value "NOP")
      (footprint "eagle-import:R0805")
      (libsource (lib "eagle-import") (part "R-US_R0805"))
    )
    (comp (ref "R9")
      (value "538")
      (footprint "eagle-import:R0805")
      (libsource (lib "eagle-import") (part "R-US_R0805"))
    )
    (comp (ref "R10")
      (value "17.3k")
      (footprint "eagle-import:R0805")
      (libsource (lib "eagle-import") (part "R-US_R0805"))
    )
    (comp (ref "R11")
      (value "NOP")
      (footprint "eagle-import:R0805")
      (libsource (lib "eagle-import") (part "R-US_R0805"))
    )
    (comp (ref "R14")
      (value "10k")
      (footprint "eagle-import:R0805")
      (libsource (lib "eagle-import") (part "R-US_R0805"))
    )
    (comp (ref "R15")
      (value "200k")
      (footprint "eagle-import:R0805")
      (libsource (lib "eagle-import") (part "R-US_R0805"))
    )
    (comp (ref "R16")
      (value "4.99k")
      (footprint "eagle-import:R0805")
      (libsource (lib "eagle-import") (part "R-US_R0805"))
    )
    (comp (ref "R17")
      (value "4.99k")
      (footprint "eagle-import:R0805")
      (libsource (lib "eagle-import") (part "R-US_R0805"))
    )
    (comp (ref "R18")
      (value "200k")
      (footprint "eagle-import:R0805")
      (libsource (lib "eagle-import") (part "R-US_R0805"))
    )
    (comp (ref "R19")
      (value "50")
      (footprint "eagle-import:R0805")
      (libsource (lib "eagle-import") (part "R-US_R0805"))
    )
    (comp (ref "R20")
      (value "NOP")
      (footprint "eagle-import:R0805")
      (libsource (lib "eagle-import") (part "R-US_R0805"))
    )
    (comp (ref "C4")
      (value "100n")
      (footprint "eagle-import:C0805")
      (libsource (lib "eagle-import") (part "C-USC0805"))
    )
    (comp (ref "C19")
      (value "100n")
      (footprint "eagle-import:C0805")
      (libsource (lib "eagle-import") (part "C-USC0805"))
    )
    (comp (ref "C20")
      (value "10u")
      (footprint "eagle-import:C0805")
      (libsource (lib "eagle-import") (part "C-USC0805"))
    )
    (comp (ref "C21")
      (value "100n")
      (footprint "eagle-import:C0805")
      (libsource (lib "eagle-import") (part "C-USC0805"))
    )
    (comp (ref "C22")
      (value "44u")
      (footprint "eagle-import:C0805")
      (libsource (lib "eagle-import") (part "C-USC0805"))
    )
    (comp (ref "C28")
      (value "11n")
      (footprint "eagle-import:C0805")
      (libsource (lib "eagle-import") (part "C-USC0805"))
    )
    (comp (ref "C29")
      (value "1.1n")
      (footprint "eagle-import:C0805")
      (libsource (lib "eagle-import") (part "C-USC0805"))
    )
    (comp (ref "C30")
      (value "11n")
      (footprint "eagle-import:C0805")
      (libsource (lib "eagle-import") (part "C-USC0805"))
    )
    (comp (ref "C31")
      (value "1.1n")
      (footprint "eagle-import:C0805")
      (libsource (lib "eagle-import") (part "C-USC0805"))
    )
    (comp (ref "C32")
      (value "2.2u")
      (footprint "eagle-import:C0805")
      (libsource (lib "eagle-import") (part "C-USC0805"))
    )
    (comp (ref "C33")
      (value "10p")
      (footprint "eagle-import:C0805")
      (libsource (lib "eagle-import") (part "C-USC0805"))
    )
    (comp (ref "C34")
      (value "10p")
      (footprint "eagle-import:C0805")
      (libsource (lib "eagle-import") (part "C-USC0805"))
    )
    (comp (ref "C35")
      (value "10p")
      (footprint "eagle-import:C0805")
      (libsource (lib "eagle-import") (part "C-USC0805"))
    )
    (comp (ref "C36")
      (value "10p")
      (footprint "eagle-import:C0805")
      (libsource (lib "eagle-import") (part "C-USC0805"))
    )
    (comp (ref "IC5")
      (value "MCP4017T-104E_LT")
      (footprint "eagle-import:SOT65P210X110-6N")
      (fields
        (field (name "MANUFACTURER_PART_NUMBER") "MCP4017T-104E/LT")
        (field (name "MOUSER_PART_NUMBER") "579-MCP4017T104E/LT")
        (field (name "RS_PART_NUMBER") "7386799P")
      )
      (libsource (lib "eagle-import") (part "MCP4017T-104E_LT"))
    )
    (comp (ref "IC6")
      (value "LT6230CS6#TRMPBF")
      (footprint "eagle-import:SOT95P280X100-6N")
      (fields
        (field (name "MOUSER_PART_NUMBER") "584-LT6230CS6#TRMPBF")
        (field (name "RS_PART_NUMBER") "5061202P")
      )
      (libsource (lib "eagle-import") (part "LT6230CS6#TRMPBF"))
    )
    (comp (ref "IC9")
      (value "LTC6242HVCGN#PBF")
      (footprint "eagle-import:SOP64P601X175-16N")
      (fields (field (name "MOUSER_PART_NUMBER") "584-LTC6242HVCGN#PBF"))
      (libsource (lib "eagle-import") (part "LTC6242HVCGN#PBF"))
    )
    (comp (ref "R13")
      (value "4.7k")
      (footprint "eagle-import:R0805")
      (libsource (lib "eagle-import") (part "R-US_R0805"))
    )
    (comp (ref "R21")
      (value "1k")
      (footprint "eagle-import:R0805")
      (libsource (lib "eagle-import") (part "R-US_R0805"))
    )
    (comp (ref "R22")
      (value "1.5k")
      (footprint "eagle-import:R0805")
      (libsource (lib "eagle-import") (part "R-US_R0805"))
    )
    (comp (ref "R23")
      (value "50")
      (footprint "eagle-import:R0805")
      (libsource (lib "eagle-import") (part "R-US_R0805"))
    )
    (comp (ref "R28")
      (value "1.61k")
      (footprint "eagle-import:R0805")
      (libsource (lib "eagle-import") (part "R-US_R0805"))
    )
    (comp (ref "R29")
      (value "5.77k")
      (footprint "eagle-import:R0805")
      (libsource (lib "eagle-import") (part "R-US_R0805"))
    )
    (comp (ref "R30")
      (value "NOP")
      (footprint "eagle-import:R0805")
      (libsource (lib "eagle-import") (part "R-US_R0805"))
    )
    (comp (ref "R31")
      (value "538")
      (footprint "eagle-import:R0805")
      (libsource (lib "eagle-import") (part "R-US_R0805"))
    )
    (comp (ref "R32")
      (value "17.3k")
      (footprint "eagle-import:R0805")
      (libsource (lib "eagle-import") (part "R-US_R0805"))
    )
    (comp (ref "R33")
      (value "NOP")
      (footprint "eagle-import:R0805")
      (libsource (lib "eagle-import") (part "R-US_R0805"))
    )
    (comp (ref "R34")
      (value "10k")
      (footprint "eagle-import:R0805")
      (libsource (lib "eagle-import") (part "R-US_R0805"))
    )
    (comp (ref "R35")
      (value "200k")
      (footprint "eagle-import:R0805")
      (libsource (lib "eagle-import") (part "R-US_R0805"))
    )
    (comp (ref "R36")
      (value "4.99k")
      (footprint "eagle-import:R0805")
      (libsource (lib "eagle-import") (part "R-US_R0805"))
    )
    (comp (ref "R37")
      (value "4.99k")
      (footprint "eagle-import:R0805")
      (libsource (lib "eagle-import") (part "R-US_R0805"))
    )
    (comp (ref "R38")
      (value "200k")
      (footprint "eagle-import:R0805")
      (libsource (lib "eagle-import") (part "R-US_R0805"))
    )
    (comp (ref "R39")
      (value "NOP")
      (footprint "eagle-import:R0805")
      (libsource (lib "eagle-import") (part "R-US_R0805"))
    )
    (comp (ref "C50")
      (value "2.2n")
      (footprint "eagle-import:C0805")
      (libsource (lib "eagle-import") (part "C-USC0805"))
    )
    (comp (ref "C51")
      (value "2.2n")
      (footprint "eagle-import:C0805")
      (libsource (lib "eagle-import") (part "C-USC0805"))
    )
    (comp (ref "C52")
      (value "2.2n")
      (footprint "eagle-import:C0805")
      (libsource (lib "eagle-import") (part "C-USC0805"))
    )
    (comp (ref "U1")
      (value "ADS1174IPAPT")
      (footprint "eagle-import:QFP50P1200X1200X120-65N")
      (fields (field (name "MF") "Texas Instruments"))
      (libsource (lib "eagle-import") (part "ADS1174IPAPT"))
    )
  )
  (nets
    (net (code "1") (name "0") (class "Default")
      (node (ref "C1") (pin "2") (pinfunction "2_2") (pintype "passive"))
      (node (ref "C15") (pin "2") (pinfunction "2_2") (pintype "passive"))
      (node (ref "C16") (pin "2") (pinfunction "2_2") (pintype "passive"))
      (node (ref "C17") (pin "2") (pinfunction "2_2") (pintype "passive"))
      (node (ref "C18") (pin "2") (pinfunction "2_2") (pintype "passive"))
      (node (ref "C19") (pin "2") (pinfunction "2_2") (pintype "passive"))
      (node (ref "C21") (pin "2") (pinfunction "2_2") (pintype "passive"))
      (node (ref "C23") (pin "2") (pinfunction "2_2") (pintype "passive"))
      (node (ref "C25") (pin "2") (pinfunction "2_2") (pintype "passive"))
      (node (ref "C27") (pin "2") (pinfunction "2_2") (pintype "passive"))
      (node (ref "C3") (pin "2") (pinfunction "2_2") (pintype "passive"))
      (node (ref "C37") (pin "2") (pinfunction "2_2") (pintype "passive"))
      (node (ref "C4") (pin "2") (pinfunction "2_2") (pintype "passive"))
      (node (ref "C47") (pin "2") (pinfunction "2_2") (pintype "passive"))
      (node (ref "C48") (pin "2") (pinfunction "2_2") (pintype "passive"))
      (node (ref "C49") (pin "2") (pinfunction "2_2") (pintype "passive"))
      (node (ref "IC1") (pin "2") (pinfunction "V-_2") (pintype "power_in"))
      (node (ref "IC1") (pin "5") (pinfunction "~{ENABLE}_5") (pintype "bidirectional"))
      (node (ref "IC10") (pin "13") (pinfunction "V-_13") (pintype "bidirectional"))
      (node (ref "IC11") (pin "2") (pinfunction "GND_2") (pintype "bidirectional"))
      (node (ref "IC12") (pin "2") (pinfunction "GND_2") (pintype "bidirectional"))
      (node (ref "IC2") (pin "2") (pinfunction "VSS_2") (pintype "bidirectional"))
      (node (ref "IC3") (pin "13") (pinfunction "V-_13") (pintype "bidirectional"))
      (node (ref "IC4") (pin "2") (pinfunction "VDD_2") (pintype "power_in"))
      (node (ref "IC5") (pin "2") (pinfunction "VSS_2") (pintype "bidirectional"))
      (node (ref "IC6") (pin "2") (pinfunction "V-_2") (pintype "power_in"))
      (node (ref "IC6") (pin "5") (pinfunction "~{ENABLE}_5") (pintype "bidirectional"))
      (node (ref "IC7") (pin "2") (pinfunction "VSS_2") (pintype "bidirectional"))
      (node (ref "IC8") (pin "2") (pinfunction "V-_2") (pintype "power_in"))
      (node (ref "IC8") (pin "5") (pinfunction "~{ENABLE}_5") (pintype "bidirectional"))
      (node (ref "IC9") (pin "13") (pinfunction "V-_13") (pintype "bidirectional"))
      (node (ref "R7") (pin "1") (pinfunction "1_1") (pintype "passive"))
      (node (ref "ST1") (pin "2") (pinfunction "2_2") (pintype "bidirectional"))
      (node (ref "U1") (pin "21") (pinfunction "DGND_21") (pintype "power_in"))
      (node (ref "U1") (pin "24") (pinfunction "DGND_24") (pintype "power_in"))
      (node (ref "U1") (pin "25") (pinfunction "DGND_25") (pintype "power_in"))
      (node (ref "U1") (pin "35") (pinfunction "~{PWDN8}_35") (pintype "input"))
      (node (ref "U1") (pin "36") (pinfunction "~{PWDN7}_36") (pintype "input"))
      (node (ref "U1") (pin "37") (pinfunction "~{PWDN6}_37") (pintype "input"))
      (node (ref "U1") (pin "38") (pinfunction "~{PWDN5}_38") (pintype "input"))
      (node (ref "U1") (pin "43") (pinfunction "AGND_43") (pintype "power_in"))
      (node (ref "U1") (pin "54") (pinfunction "AGND_54") (pintype "power_in"))
      (node (ref "U1") (pin "57") (pinfunction "VREFN_57") (pintype "input"))
      (node (ref "U1") (pin "58") (pinfunction "AGND_58") (pintype "power_in"))
      (node (ref "U1") (pin "59") (pinfunction "AGND_59") (pintype "power_in"))
      (node (ref "U1") (pin "6") (pinfunction "AGND_6") (pintype "power_in"))
      (node (ref "U1") (pin "7") (pinfunction "DGND_7") (pintype "power_in"))
    )
    (net (code "2") (name "1V8") (class "Default")
      (node (ref "C47") (pin "1") (pinfunction "1_1") (pintype "passive"))
      (node (ref "IC11") (pin "1") (pinfunction "OUT_1") (pintype "bidirectional"))
      (node (ref "U1") (pin "26") (pinfunction "DVDD_26") (pintype "power_in"))
    )
    (net (code "3") (name "3V3A") (class "Default")
      (node (ref "C1") (pin "1") (pinfunction "1_1") (pintype "passive"))
      (node (ref "C16") (pin "1") (pinfunction "1_1") (pintype "passive"))
      (node (ref "C18") (pin "1") (pinfunction "1_1") (pintype "passive"))
      (node (ref "C19") (pin "1") (pinfunction "1_1") (pintype "passive"))
      (node (ref "C23") (pin "1") (pinfunction "1_1") (pintype "passive"))
      (node (ref "C27") (pin "1") (pinfunction "1_1") (pintype "passive"))
      (node (ref "C37") (pin "1") (pinfunction "1_1") (pintype "passive"))
      (node (ref "C4") (pin "1") (pinfunction "1_1") (pintype "passive"))
      (node (ref "IC1") (pin "6") (pinfunction "V+_6") (pintype "power_in"))
      (node (ref "IC10") (pin "4") (pinfunction "V+_4") (pintype "bidirectional"))
      (node (ref "IC12") (pin "5") (pinfunction "OUT_5") (pintype "bidirectional"))
      (node (ref "IC3") (pin "4") (pinfunction "V+_4") (pintype "bidirectional"))
      (node (ref "IC4") (pin "5") (pinfunction "VCC_5") (pintype "power_in"))
      (node (ref "IC6") (pin "6") (pinfunction "V+_6") (pintype "power_in"))
      (node (ref "IC8") (pin "6") (pinfunction "V+_6") (pintype "power_in"))
      (node (ref "IC9") (pin "4") (pinfunction "V+_4") (pintype "bidirectional"))
      (node (ref "R8") (pin "2") (pinfunction "2_2") (pintype "passive"))
      (node (ref "U1") (pin "22") (pinfunction "IOVDD_22") (pintype "power_in"))
      (node (ref "U1") (pin "23") (pinfunction "IOVDD_23") (pintype "power_in"))
      (node (ref "U1") (pin "56") (pinfunction "VREFP_56") (pintype "input"))
    )
    (net (code "4") (name "5V") (class "Default")
      (node (ref "C15") (pin "1") (pinfunction "1_1") (pintype "passive"))
      (node (ref "C48") (pin "1") (pinfunction "1_1") (pintype "passive"))
      (node (ref "IC11") (pin "4") (pinfunction "EN_4") (pintype "bidirectional"))
      (node (ref "IC11") (pin "6") (pinfunction "IN_6") (pintype "bidirectional"))
      (node (ref "IC12") (pin "1") (pinfunction "IN_1") (pintype "bidirectional"))
      (node (ref "IC12") (pin "3") (pinfunction "EN_3") (pintype "bidirectional"))
      (node (ref "ST1") (pin "1") (pinfunction "1_1") (pintype "bidirectional"))
      (node (ref "U1") (pin "44") (pinfunction "AVDD_44") (pintype "power_in"))
      (node (ref "U1") (pin "5") (pinfunction "AVDD_5") (pintype "power_in"))
      (node (ref "U1") (pin "53") (pinfunction "AVDD_53") (pintype "power_in"))
      (node (ref "U1") (pin "60") (pinfunction "AVDD_60") (pintype "power_in"))
    )
    (net (code "5") (name "CLK") (class "Default")
      (node (ref "R65") (pin "2") (pinfunction "2_2") (pintype "passive"))
      (node (ref "U1") (pin "27") (pinfunction "CLK_27") (pintype "input"))
    )
    (net (code "6") (name "CLKDLV") (class "Default")
      (node (ref "R64") (pin "2") (pinfunction "2_2") (pintype "passive"))
      (node (ref "U1") (pin "10") (pinfunction "CLKDLV_10") (pintype "input"))
    )
    (net (code "7") (name "DATA1") (class "Default")
      (node (ref "R68") (pin "2") (pinfunction "2_2") (pintype "passive"))
      (node (ref "U1") (pin "20") (pinfunction "DOUT1_20") (pintype "output"))
    )
    (net (code "8") (name "DATA2") (class "Default")
      (node (ref "R71") (pin "2") (pinfunction "2_2") (pintype "passive"))
      (node (ref "U1") (pin "19") (pinfunction "DOUT2_19") (pintype "output"))
    )
    (net (code "9") (name "DATA3") (class "Default")
      (node (ref "R69") (pin "1") (pinfunction "1_1") (pintype "passive"))
      (node (ref "U1") (pin "18") (pinfunction "DOUT3_18") (pintype "output"))
    )
    (net (code "10") (name "DATA4") (class "Default")
      (node (ref "R70") (pin "1") (pinfunction "1_1") (pintype "passive"))
      (node (ref "U1") (pin "17") (pinfunction "DOUT4_17") (pintype "output"))
    )
    (net (code "11") (name "DIN") (class "Default")
      (node (ref "R60") (pin "1") (pinfunction "1_1") (pintype "passive"))
      (node (ref "U1") (pin "12") (pinfunction "DIN_12") (pintype "input"))
    )
    (net (code "12") (name "DRDY_BAR{slash}FSYNC") (class "Default")
      (node (ref "R67") (pin "2") (pinfunction "2_2") (pintype "passive"))
      (node (ref "U1") (pin "29") (pinfunction "~{DRDY}/FSYNC_29") (pintype "bidirectional"))
    )
    (net (code "13") (name "EXP_PAD") (class "Default")
      (node (ref "U1") (pin "65") (pinfunction "EXP_PAD_65") (pintype "power_in"))
    )
    (net (code "14") (name "FMT0") (class "Default")
      (node (ref "R61") (pin "1") (pinfunction "1_1") (pintype "passive"))
      (node (ref "U1") (pin "32") (pinfunction "FORMAT0_32") (pintype "input"))
    )
    (net (code "15") (name "FMT1") (class "Default")
      (node (ref "R62") (pin "1") (pinfunction "1_1") (pintype "passive"))
      (node (ref "U1") (pin "31") (pinfunction "FORMAT1_31") (pintype "input"))
    )
    (net (code "16") (name "FMT2") (class "Default")
      (node (ref "R63") (pin "1") (pinfunction "1_1") (pintype "passive"))
      (node (ref "U1") (pin "30") (pinfunction "FORMAT2_30") (pintype "input"))
    )
    (net (code "17") (name "I2C_SCL_1") (class "Default")
      (node (ref "IC2") (pin "3") (pinfunction "SCL_3") (pintype "bidirectional"))
      (node (ref "JP3") (pin "2") (pinfunction "2_2") (pintype "passive"))
      (node (ref "JP7") (pin "2") (pinfunction "2_2") (pintype "passive"))
    )
    (net (code "18") (name "I2C_SCL_2") (class "Default")
      (node (ref "IC5") (pin "3") (pinfunction "SCL_3") (pintype "bidirectional"))
      (node (ref "JP3") (pin "12") (pinfunction "12_12") (pintype "passive"))
      (node (ref "JP7") (pin "12") (pinfunction "12_12") (pintype "passive"))
    )
    (net (code "19") (name "I2C_SCL_3") (class "Default")
      (node (ref "IC7") (pin "3") (pinfunction "SCL_3") (pintype "bidirectional"))
      (node (ref "JP3") (pin "8") (pinfunction "8_8") (pintype "passive"))
      (node (ref "JP7") (pin "8") (pinfunction "8_8") (pintype "passive"))
    )
    (net (code "20") (name "I2C_SDA_1") (class "Default")
      (node (ref "IC2") (pin "4") (pinfunction "SDA_4") (pintype "bidirectional"))
      (node (ref "JP3") (pin "4") (pinfunction "4_4") (pintype "passive"))
      (node (ref "JP7") (pin "4") (pinfunction "4_4") (pintype "passive"))
    )
    (net (code "21") (name "I2C_SDA_2") (class "Default")
      (node (ref "IC5") (pin "4") (pinfunction "SDA_4") (pintype "bidirectional"))
      (node (ref "JP3") (pin "10") (pinfunction "10_10") (pintype "passive"))
      (node (ref "JP7") (pin "10") (pinfunction "10_10") (pintype "passive"))
    )
    (net (code "22") (name "I2C_SDA_3") (class "Default")
      (node (ref "IC7") (pin "4") (pinfunction "SDA_4") (pintype "bidirectional"))
      (node (ref "JP3") (pin "6") (pinfunction "6_6") (pintype "passive"))
      (node (ref "JP7") (pin "6") (pinfunction "6_6") (pintype "passive"))
    )
    (net (code "23") (name "MODE") (class "Default")
      (node (ref "R56") (pin "1") (pinfunction "1_1") (pintype "passive"))
      (node (ref "U1") (pin "34") (pinfunction "MODE_34") (pintype "input"))
    )
    (net (code "24") (name "Net-(C5-Pad2)") (class "Default")
      (node (ref "C5") (pin "2") (pinfunction "2_2") (pintype "passive"))
      (node (ref "R4") (pin "2") (pinfunction "2_2") (pintype "passive"))
      (node (ref "R5") (pin "1") (pinfunction "1_1") (pintype "passive"))
      (node (ref "R6") (pin "2") (pinfunction "2_2") (pintype "passive"))
    )
    (net (code "25") (name "Net-(C7-Pad2)") (class "Default")
      (node (ref "C7") (pin "2") (pinfunction "2_2") (pintype "passive"))
      (node (ref "R10") (pin "1") (pinfunction "1_1") (pintype "passive"))
      (node (ref "R11") (pin "2") (pinfunction "2_2") (pintype "passive"))
      (node (ref "R9") (pin "2") (pinfunction "2_2") (pintype "passive"))
    )
    (net (code "26") (name "Net-(C9-Pad2)") (class "Default")
      (node (ref "C9") (pin "2") (pinfunction "2_2") (pintype "passive"))
      (node (ref "R14") (pin "2") (pinfunction "2_2") (pintype "passive"))
      (node (ref "R15") (pin "2") (pinfunction "2_2") (pintype "passive"))
    )
    (net (code "27") (name "Net-(C14-Pad2)") (class "Default")
      (node (ref "C14") (pin "2") (pinfunction "2_2") (pintype "passive"))
      (node (ref "R19") (pin "1") (pinfunction "1_1") (pintype "passive"))
    )
    (net (code "28") (name "Net-(C22-Pad2)") (class "Default")
      (node (ref "C22") (pin "2") (pinfunction "2_2") (pintype "passive"))
      (node (ref "R23") (pin "1") (pinfunction "1_1") (pintype "passive"))
    )
    (net (code "29") (name "Net-(C26-Pad2)") (class "Default")
      (node (ref "C26") (pin "2") (pinfunction "2_2") (pintype "passive"))
      (node (ref "R27") (pin "1") (pinfunction "1_1") (pintype "passive"))
    )
    (net (code "30") (name "Net-(C28-Pad2)") (class "Default")
      (node (ref "C28") (pin "2") (pinfunction "2_2") (pintype "passive"))
      (node (ref "R28") (pin "2") (pinfunction "2_2") (pintype "passive"))
      (node (ref "R29") (pin "1") (pinfunction "1_1") (pintype "passive"))
      (node (ref "R30") (pin "2") (pinfunction "2_2") (pintype "passive"))
    )
    (net (code "31") (name "Net-(C30-Pad2)") (class "Default")
      (node (ref "C30") (pin "2") (pinfunction "2_2") (pintype "passive"))
      (node (ref "R31") (pin "2") (pinfunction "2_2") (pintype "passive"))
      (node (ref "R32") (pin "1") (pinfunction "1_1") (pintype "passive"))
      (node (ref "R33") (pin "2") (pinfunction "2_2") (pintype "passive"))
    )
    (net (code "32") (name "Net-(C32-Pad2)") (class "Default")
      (node (ref "C32") (pin "2") (pinfunction "2_2") (pintype "passive"))
      (node (ref "R34") (pin "2") (pinfunction "2_2") (pintype "passive"))
      (node (ref "R35") (pin "2") (pinfunction "2_2") (pintype "passive"))
    )
    (net (code "33") (name "Net-(C38-Pad2)") (class "Default")
      (node (ref "C38") (pin "2") (pinfunction "2_2") (pintype "passive"))
      (node (ref "R40") (pin "2") (pinfunction "2_2") (pintype "passive"))
      (node (ref "R41") (pin "1") (pinfunction "1_1") (pintype "passive"))
      (node (ref "R42") (pin "2") (pinfunction "2_2") (pintype "passive"))
    )
    (net (code "34") (name "Net-(C40-Pad2)") (class "Default")
      (node (ref "C40") (pin "2") (pinfunction "2_2") (pintype "passive"))
      (node (ref "R43") (pin "2") (pinfunction "2_2") (pintype "passive"))
      (node (ref "R44") (pin "1") (pinfunction "1_1") (pintype "passive"))
      (node (ref "R45") (pin "2") (pinfunction "2_2") (pintype "passive"))
    )
    (net (code "35") (name "Net-(C42-Pad2)") (class "Default")
      (node (ref "C42") (pin "2") (pinfunction "2_2") (pintype "passive"))
      (node (ref "R46") (pin "2") (pinfunction "2_2") (pintype "passive"))
      (node (ref "R47") (pin "2") (pinfunction "2_2") (pintype "passive"))
    )
    (net (code "36") (name "Net-(IC1-+IN)") (class "Default")
      (node (ref "C2") (pin "2") (pinfunction "2_2") (pintype "passive"))
      (node (ref "IC1") (pin "3") (pinfunction "+IN_3") (pintype "input"))
      (node (ref "R1") (pin "1") (pinfunction "1_1") (pintype "passive"))
    )
    (net (code "37") (name "Net-(IC1--IN)") (class "Default")
      (node (ref "C14") (pin "1") (pinfunction "1_1") (pintype "passive"))
      (node (ref "IC1") (pin "4") (pinfunction "-IN_4") (pintype "input"))
      (node (ref "IC2") (pin "5") (pinfunction "B_5") (pintype "bidirectional"))
      (node (ref "R3") (pin "1") (pinfunction "1_1") (pintype "passive"))
    )
    (net (code "38") (name "Net-(IC2-VDD)") (class "Default")
      (node (ref "C3") (pin "1") (pinfunction "1_1") (pintype "passive"))
      (node (ref "IC2") (pin "1") (pinfunction "VDD_1") (pintype "bidirectional"))
    )
    (net (code "39") (name "Net-(IC2-W)") (class "Default")
      (node (ref "IC2") (pin "6") (pinfunction "W_6") (pintype "bidirectional"))
      (node (ref "R2") (pin "1") (pinfunction "1_1") (pintype "passive"))
    )
    (net (code "40") (name "Net-(IC3-+-IN_B)") (class "Default")
      (node (ref "C7") (pin "1") (pinfunction "1_1") (pintype "passive"))
      (node (ref "C9") (pin "1") (pinfunction "1_1") (pintype "passive"))
      (node (ref "IC3") (pin "6") (pinfunction "+-IN_B_6") (pintype "bidirectional"))
      (node (ref "IC3") (pin "7") (pinfunction "OUT_B_7") (pintype "bidirectional"))
    )
    (net (code "41") (name "Net-(IC3-+IN_A)") (class "Default")
      (node (ref "C6") (pin "1") (pinfunction "1_1") (pintype "passive"))
      (node (ref "IC3") (pin "3") (pinfunction "+IN_A_3") (pintype "bidirectional"))
      (node (ref "R5") (pin "2") (pinfunction "2_2") (pintype "passive"))
    )
    (net (code "42") (name "Net-(IC3-+IN_B)") (class "Default")
      (node (ref "C8") (pin "1") (pinfunction "1_1") (pintype "passive"))
      (node (ref "IC3") (pin "5") (pinfunction "+IN_B_5") (pintype "bidirectional"))
      (node (ref "R10") (pin "2") (pinfunction "2_2") (pintype "passive"))
    )
    (net (code "43") (name "Net-(IC3-+IN_C)") (class "Default")
      (node (ref "IC3") (pin "12") (pinfunction "+IN_C_12") (pintype "bidirectional"))
      (node (ref "R18") (pin "2") (pinfunction "2_2") (pintype "passive"))
      (node (ref "R20") (pin "1") (pinfunction "1_1") (pintype "passive"))
    )
    (net (code "44") (name "Net-(IC3--IN_A)") (class "Default")
      (node (ref "C5") (pin "1") (pinfunction "1_1") (pintype "passive"))
      (node (ref "IC3") (pin "1") (pinfunction "OUT_A_1") (pintype "bidirectional"))
      (node (ref "IC3") (pin "2") (pinfunction "-IN_A_2") (pintype "bidirectional"))
      (node (ref "R9") (pin "1") (pinfunction "1_1") (pintype "passive"))
    )
    (net (code "45") (name "Net-(IC3--IN_C)") (class "Default")
      (node (ref "C10") (pin "1") (pinfunction "1_1") (pintype "passive"))
      (node (ref "IC3") (pin "11") (pinfunction "-IN_C_11") (pintype "bidirectional"))
      (node (ref "R15") (pin "1") (pinfunction "1_1") (pintype "passive"))
    )
    (net (code "46") (name "Net-(IC3--IN_D)") (class "Default")
      (node (ref "C11") (pin "2") (pinfunction "2_2") (pintype "passive"))
      (node (ref "C12") (pin "1") (pinfunction "1_1") (pintype "passive"))
      (node (ref "IC3") (pin "15") (pinfunction "-IN_D_15") (pintype "bidirectional"))
      (node (ref "R16") (pin "1") (pinfunction "1_1") (pintype "passive"))
      (node (ref "R17") (pin "2") (pinfunction "2_2") (pintype "passive"))
    )
    (net (code "47") (name "Net-(IC4-INVERTING_INPUT)") (class "Default")
      (node (ref "IC4") (pin "4") (pinfunction "INVERTING_INPUT_4") (pintype "input"))
      (node (ref "R12") (pin "2") (pinfunction "2_2") (pintype "passive"))
    )
    (net (code "48") (name "Net-(IC4-NON-INVERTING_INPUT)") (class "Default")
      (node (ref "C17") (pin "1") (pinfunction "1_1") (pintype "passive"))
      (node (ref "IC4") (pin "3") (pinfunction "NON-INVERTING_INPUT_3") (pintype "input"))
      (node (ref "R7") (pin "2") (pinfunction "2_2") (pintype "passive"))
      (node (ref "R8") (pin "1") (pinfunction "1_1") (pintype "passive"))
    )
    (net (code "49") (name "Net-(IC5-B)") (class "Default")
      (node (ref "C22") (pin "1") (pinfunction "1_1") (pintype "passive"))
      (node (ref "IC5") (pin "5") (pinfunction "B_5") (pintype "bidirectional"))
      (node (ref "IC6") (pin "4") (pinfunction "-IN_4") (pintype "input"))
      (node (ref "R22") (pin "1") (pinfunction "1_1") (pintype "passive"))
    )
    (net (code "50") (name "Net-(IC5-VDD)") (class "Default")
      (node (ref "C21") (pin "1") (pinfunction "1_1") (pintype "passive"))
      (node (ref "IC5") (pin "1") (pinfunction "VDD_1") (pintype "bidirectional"))
    )
    (net (code "51") (name "Net-(IC5-W)") (class "Default")
      (node (ref "IC5") (pin "6") (pinfunction "W_6") (pintype "bidirectional"))
      (node (ref "R21") (pin "1") (pinfunction "1_1") (pintype "passive"))
    )
    (net (code "52") (name "Net-(IC6-+IN)") (class "Default")
      (node (ref "C20") (pin "2") (pinfunction "2_2") (pintype "passive"))
      (node (ref "IC6") (pin "3") (pinfunction "+IN_3") (pintype "input"))
      (node (ref "R13") (pin "1") (pinfunction "1_1") (pintype "passive"))
    )
    (net (code "53") (name "Net-(IC7-B)") (class "Default")
      (node (ref "C26") (pin "1") (pinfunction "1_1") (pintype "passive"))
      (node (ref "IC7") (pin "5") (pinfunction "B_5") (pintype "bidirectional"))
      (node (ref "IC8") (pin "4") (pinfunction "-IN_4") (pintype "input"))
      (node (ref "R26") (pin "1") (pinfunction "1_1") (pintype "passive"))
    )
    (net (code "54") (name "Net-(IC7-VDD)") (class "Default")
      (node (ref "C25") (pin "1") (pinfunction "1_1") (pintype "passive"))
      (node (ref "IC7") (pin "1") (pinfunction "VDD_1") (pintype "bidirectional"))
    )
    (net (code "55") (name "Net-(IC7-W)") (class "Default")
      (node (ref "IC7") (pin "6") (pinfunction "W_6") (pintype "bidirectional"))
      (node (ref "R25") (pin "1") (pinfunction "1_1") (pintype "passive"))
    )
    (net (code "56") (name "Net-(IC8-+IN)") (class "Default")
      (node (ref "C24") (pin "2") (pinfunction "2_2") (pintype "passive"))
      (node (ref "IC8") (pin "3") (pinfunction "+IN_3") (pintype "input"))
      (node (ref "R24") (pin "1") (pinfunction "1_1") (pintype "passive"))
    )
    (net (code "57") (name "Net-(IC9-+-IN_B)") (class "Default")
      (node (ref "C30") (pin "1") (pinfunction "1_1") (pintype "passive"))
      (node (ref "C32") (pin "1") (pinfunction "1_1") (pintype "passive"))
      (node (ref "IC9") (pin "6") (pinfunction "+-IN_B_6") (pintype "bidirectional"))
      (node (ref "IC9") (pin "7") (pinfunction "OUT_B_7") (pintype "bidirectional"))
    )
    (net (code "58") (name "Net-(IC9-+IN_A)") (class "Default")
      (node (ref "C29") (pin "1") (pinfunction "1_1") (pintype "passive"))
      (node (ref "IC9") (pin "3") (pinfunction "+IN_A_3") (pintype "bidirectional"))
      (node (ref "R29") (pin "2") (pinfunction "2_2") (pintype "passive"))
    )
    (net (code "59") (name "Net-(IC9-+IN_B)") (class "Default")
      (node (ref "C31") (pin "1") (pinfunction "1_1") (pintype "passive"))
      (node (ref "IC9") (pin "5") (pinfunction "+IN_B_5") (pintype "bidirectional"))
      (node (ref "R32") (pin "2") (pinfunction "2_2") (pintype "passive"))
    )
    (net (code "60") (name "Net-(IC9-+IN_C)") (class "Default")
      (node (ref "IC9") (pin "12") (pinfunction "+IN_C_12") (pintype "bidirectional"))
      (node (ref "R38") (pin "2") (pinfunction "2_2") (pintype "passive"))
      (node (ref "R39") (pin "1") (pinfunction "1_1") (pintype "passive"))
    )
    (net (code "61") (name "Net-(IC9--IN_A)") (class "Default")
      (node (ref "C28") (pin "1") (pinfunction "1_1") (pintype "passive"))
      (node (ref "IC9") (pin "1") (pinfunction "OUT_A_1") (pintype "bidirectional"))
      (node (ref "IC9") (pin "2") (pinfunction "-IN_A_2") (pintype "bidirectional"))
      (node (ref "R31") (pin "1") (pinfunction "1_1") (pintype "passive"))
    )
    (net (code "62") (name "Net-(IC9--IN_C)") (class "Default")
      (node (ref "C33") (pin "1") (pinfunction "1_1") (pintype "passive"))
      (node (ref "IC9") (pin "11") (pinfunction "-IN_C_11") (pintype "bidirectional"))
      (node (ref "R35") (pin "1") (pinfunction "1_1") (pintype "passive"))
    )
    (net (code "63") (name "Net-(IC9--IN_D)") (class "Default")
      (node (ref "C34") (pin "2") (pinfunction "2_2") (pintype "passive"))
      (node (ref "C35") (pin "1") (pinfunction "1_1") (pintype "passive"))
      (node (ref "IC9") (pin "15") (pinfunction "-IN_D_15") (pintype "bidirectional"))
      (node (ref "R36") (pin "1") (pinfunction "1_1") (pintype "passive"))
      (node (ref "R37") (pin "2") (pinfunction "2_2") (pintype "passive"))
    )
    (net (code "64") (name "Net-(IC10-+-IN_B)") (class "Default")
      (node (ref "C40") (pin "1") (pinfunction "1_1") (pintype "passive"))
      (node (ref "C42") (pin "1") (pinfunction "1_1") (pintype "passive"))
      (node (ref "IC10") (pin "6") (pinfunction "+-IN_B_6") (pintype "bidirectional"))
      (node (ref "IC10") (pin "7") (pinfunction "OUT_B_7") (pintype "bidirectional"))
    )
    (net (code "65") (name "Net-(IC10-+IN_A)") (class "Default")
      (node (ref "C39") (pin "1") (pinfunction "1_1") (pintype "passive"))
      (node (ref "IC10") (pin "3") (pinfunction "+IN_A_3") (pintype "bidirectional"))
      (node (ref "R41") (pin "2") (pinfunction "2_2") (pintype "passive"))
    )
    (net (code "66") (name "Net-(IC10-+IN_B)") (class "Default")
      (node (ref "C41") (pin "1") (pinfunction "1_1") (pintype "passive"))
      (node (ref "IC10") (pin "5") (pinfunction "+IN_B_5") (pintype "bidirectional"))
      (node (ref "R44") (pin "2") (pinfunction "2_2") (pintype "passive"))
    )
    (net (code "67") (name "Net-(IC10-+IN_C)") (class "Default")
      (node (ref "IC10") (pin "12") (pinfunction "+IN_C_12") (pintype "bidirectional"))
      (node (ref "R50") (pin "2") (pinfunction "2_2") (pintype "passive"))
      (node (ref "R51") (pin "1") (pinfunction "1_1") (pintype "passive"))
    )
    (net (code "68") (name "Net-(IC10--IN_A)") (class "Default")
      (node (ref "C38") (pin "1") (pinfunction "1_1") (pintype "passive"))
      (node (ref "IC10") (pin "1") (pinfunction "OUT_A_1") (pintype "bidirectional"))
      (node (ref "IC10") (pin "2") (pinfunction "-IN_A_2") (pintype "bidirectional"))
      (node (ref "R43") (pin "1") (pinfunction "1_1") (pintype "passive"))
    )
    (net (code "69") (name "Net-(IC10--IN_C)") (class "Default")
      (node (ref "C43") (pin "1") (pinfunction "1_1") (pintype "passive"))
      (node (ref "IC10") (pin "11") (pinfunction "-IN_C_11") (pintype "bidirectional"))
      (node (ref "R47") (pin "1") (pinfunction "1_1") (pintype "passive"))
    )
    (net (code "70") (name "Net-(IC10--IN_D)") (class "Default")
      (node (ref "C44") (pin "2") (pinfunction "2_2") (pintype "passive"))
      (node (ref "C45") (pin "1") (pinfunction "1_1") (pintype "passive"))
      (node (ref "IC10") (pin "15") (pinfunction "-IN_D_15") (pintype "bidirectional"))
      (node (ref "R48") (pin "1") (pinfunction "1_1") (pintype "passive"))
      (node (ref "R49") (pin "2") (pinfunction "2_2") (pintype "passive"))
    )
    (net (code "71") (name "Net-(IC11-NR{slash}FB)") (class "Default")
      (node (ref "C49") (pin "1") (pinfunction "1_1") (pintype "passive"))
      (node (ref "IC11") (pin "3") (pinfunction "NR/FB_3") (pintype "bidirectional"))
    )
    (net (code "72") (name "Net-(JP1-Pad1)") (class "Default")
      (node (ref "JP1") (pin "1") (pinfunction "1_1") (pintype "passive"))
      (node (ref "JP5") (pin "1") (pinfunction "1_1") (pintype "passive"))
      (node (ref "R52") (pin "1") (pinfunction "1_1") (pintype "passive"))
    )
    (net (code "73") (name "Net-(JP1-Pad2)") (class "Default")
      (node (ref "JP1") (pin "2") (pinfunction "2_2") (pintype "passive"))
      (node (ref "JP5") (pin "2") (pinfunction "2_2") (pintype "passive"))
      (node (ref "R67") (pin "1") (pinfunction "1_1") (pintype "passive"))
    )
    (net (code "74") (name "Net-(JP1-Pad3)") (class "Default")
      (node (ref "JP1") (pin "3") (pinfunction "3_3") (pintype "passive"))
      (node (ref "JP5") (pin "3") (pinfunction "3_3") (pintype "passive"))
      (node (ref "R53") (pin "1") (pinfunction "1_1") (pintype "passive"))
    )
    (net (code "75") (name "Net-(JP1-Pad4)") (class "Default")
      (node (ref "JP1") (pin "4") (pinfunction "4_4") (pintype "passive"))
      (node (ref "JP5") (pin "4") (pinfunction "4_4") (pintype "passive"))
      (node (ref "R66") (pin "1") (pinfunction "1_1") (pintype "passive"))
    )
    (net (code "76") (name "Net-(JP1-Pad5)") (class "Default")
      (node (ref "JP1") (pin "5") (pinfunction "5_5") (pintype "passive"))
      (node (ref "JP5") (pin "5") (pinfunction "5_5") (pintype "passive"))
      (node (ref "R54") (pin "1") (pinfunction "1_1") (pintype "passive"))
    )
    (net (code "77") (name "Net-(JP1-Pad6)") (class "Default")
      (node (ref "JP1") (pin "6") (pinfunction "6_6") (pintype "passive"))
      (node (ref "JP5") (pin "6") (pinfunction "6_6") (pintype "passive"))
      (node (ref "R65") (pin "1") (pinfunction "1_1") (pintype "passive"))
    )
    (net (code "78") (name "Net-(JP1-Pad7)") (class "Default")
      (node (ref "JP1") (pin "7") (pinfunction "7_7") (pintype "passive"))
      (node (ref "JP5") (pin "7") (pinfunction "7_7") (pintype "passive"))
      (node (ref "R55") (pin "1") (pinfunction "1_1") (pintype "passive"))
    )
    (net (code "79") (name "Net-(JP1-Pad8)") (class "Default")
      (node (ref "JP1") (pin "8") (pinfunction "8_8") (pintype "passive"))
      (node (ref "JP5") (pin "8") (pinfunction "8_8") (pintype "passive"))
      (node (ref "R64") (pin "1") (pinfunction "1_1") (pintype "passive"))
    )
    (net (code "80") (name "Net-(JP1-Pad9)") (class "Default")
      (node (ref "JP1") (pin "9") (pinfunction "9_9") (pintype "passive"))
      (node (ref "JP5") (pin "9") (pinfunction "9_9") (pintype "passive"))
      (node (ref "R59") (pin "2") (pinfunction "2_2") (pintype "passive"))
    )
    (net (code "81") (name "Net-(JP1-Pad10)") (class "Default")
      (node (ref "JP1") (pin "10") (pinfunction "10_10") (pintype "passive"))
      (node (ref "JP5") (pin "10") (pinfunction "10_10") (pintype "passive"))
      (node (ref "R60") (pin "2") (pinfunction "2_2") (pintype "passive"))
    )
    (net (code "82") (name "Net-(JP1-Pad11)") (class "Default")
      (node (ref "JP1") (pin "11") (pinfunction "11_11") (pintype "passive"))
      (node (ref "JP5") (pin "11") (pinfunction "11_11") (pintype "passive"))
      (node (ref "R58") (pin "2") (pinfunction "2_2") (pintype "passive"))
    )
    (net (code "83") (name "Net-(JP1-Pad12)") (class "Default")
      (node (ref "JP1") (pin "12") (pinfunction "12_12") (pintype "passive"))
      (node (ref "JP5") (pin "12") (pinfunction "12_12") (pintype "passive"))
      (node (ref "R61") (pin "2") (pinfunction "2_2") (pintype "passive"))
    )
    (net (code "84") (name "Net-(JP1-Pad13)") (class "Default")
      (node (ref "JP1") (pin "13") (pinfunction "13_13") (pintype "passive"))
      (node (ref "JP5") (pin "13") (pinfunction "13_13") (pintype "passive"))
      (node (ref "R57") (pin "2") (pinfunction "2_2") (pintype "passive"))
    )
    (net (code "85") (name "Net-(JP1-Pad14)") (class "Default")
      (node (ref "JP1") (pin "14") (pinfunction "14_14") (pintype "passive"))
      (node (ref "JP5") (pin "14") (pinfunction "14_14") (pintype "passive"))
      (node (ref "R62") (pin "2") (pinfunction "2_2") (pintype "passive"))
    )
    (net (code "86") (name "Net-(JP1-Pad15)") (class "Default")
      (node (ref "JP1") (pin "15") (pinfunction "15_15") (pintype "passive"))
      (node (ref "JP5") (pin "15") (pinfunction "15_15") (pintype "passive"))
      (node (ref "R56") (pin "2") (pinfunction "2_2") (pintype "passive"))
    )
    (net (code "87") (name "Net-(JP1-Pad16)") (class "Default")
      (node (ref "JP1") (pin "16") (pinfunction "16_16") (pintype "passive"))
      (node (ref "JP5") (pin "16") (pinfunction "16_16") (pintype "passive"))
      (node (ref "R63") (pin "2") (pinfunction "2_2") (pintype "passive"))
    )
    (net (code "88") (name "Net-(JP2-Pad1)") (class "Default")
      (node (ref "JP2") (pin "1") (pinfunction "1_1") (pintype "passive"))
      (node (ref "JP6") (pin "1") (pinfunction "1_1") (pintype "passive"))
      (node (ref "R68") (pin "1") (pinfunction "1_1") (pintype "passive"))
    )
    (net (code "89") (name "Net-(JP2-Pad2)") (class "Default")
      (node (ref "JP2") (pin "2") (pinfunction "2_2") (pintype "passive"))
      (node (ref "JP6") (pin "2") (pinfunction "2_2") (pintype "passive"))
      (node (ref "R71") (pin "1") (pinfunction "1_1") (pintype "passive"))
    )
    (net (code "90") (name "Net-(JP2-Pad3)") (class "Default")
      (node (ref "JP2") (pin "3") (pinfunction "3_3") (pintype "passive"))
      (node (ref "JP6") (pin "3") (pinfunction "3_3") (pintype "passive"))
      (node (ref "R69") (pin "2") (pinfunction "2_2") (pintype "passive"))
    )
    (net (code "91") (name "Net-(JP2-Pad4)") (class "Default")
      (node (ref "JP2") (pin "4") (pinfunction "4_4") (pintype "passive"))
      (node (ref "JP6") (pin "4") (pinfunction "4_4") (pintype "passive"))
      (node (ref "R70") (pin "2") (pinfunction "2_2") (pintype "passive"))
    )
    (net (code "92") (name "PWDN1") (class "Default")
      (node (ref "R52") (pin "2") (pinfunction "2_2") (pintype "passive"))
      (node (ref "U1") (pin "42") (pinfunction "~{PWDN1}_42") (pintype "input"))
    )
    (net (code "93") (name "PWDN2") (class "Default")
      (node (ref "R53") (pin "2") (pinfunction "2_2") (pintype "passive"))
      (node (ref "U1") (pin "41") (pinfunction "~{PWDN2}_41") (pintype "input"))
    )
    (net (code "94") (name "PWDN3") (class "Default")
      (node (ref "R54") (pin "2") (pinfunction "2_2") (pintype "passive"))
      (node (ref "U1") (pin "40") (pinfunction "~{PWDN3}_40") (pintype "input"))
    )
    (net (code "95") (name "PWDN4") (class "Default")
      (node (ref "R55") (pin "2") (pinfunction "2_2") (pintype "passive"))
      (node (ref "U1") (pin "39") (pinfunction "~{PWDN4}_39") (pintype "input"))
    )
    (net (code "96") (name "RX_1") (class "Default")
      (node (ref "C2") (pin "1") (pinfunction "1_1") (pintype "passive"))
      (node (ref "JP4") (pin "1") (pinfunction "1_1") (pintype "passive"))
      (node (ref "JP8") (pin "1") (pinfunction "1_1") (pintype "passive"))
    )
    (net (code "97") (name "RX_1_IF+") (class "Default")
      (node (ref "C12") (pin "2") (pinfunction "2_2") (pintype "passive"))
      (node (ref "C50") (pin "2") (pinfunction "2_2") (pintype "passive"))
      (node (ref "IC3") (pin "16") (pinfunction "OUT_D_16") (pintype "bidirectional"))
      (node (ref "JP3") (pin "11") (pinfunction "11_11") (pintype "passive"))
      (node (ref "JP7") (pin "11") (pinfunction "11_11") (pintype "passive"))
      (node (ref "R17") (pin "1") (pinfunction "1_1") (pintype "passive"))
      (node (ref "R18") (pin "1") (pinfunction "1_1") (pintype "passive"))
      (node (ref "U1") (pin "3") (pinfunction "AINP1_3") (pintype "input"))
    )
    (net (code "98") (name "RX_1_IF-") (class "Default")
      (node (ref "C10") (pin "2") (pinfunction "2_2") (pintype "passive"))
      (node (ref "C11") (pin "1") (pinfunction "1_1") (pintype "passive"))
      (node (ref "C13") (pin "1") (pinfunction "1_1") (pintype "passive"))
      (node (ref "C50") (pin "1") (pinfunction "1_1") (pintype "passive"))
      (node (ref "IC3") (pin "10") (pinfunction "OUT_C_10") (pintype "bidirectional"))
      (node (ref "JP3") (pin "9") (pinfunction "9_9") (pintype "passive"))
      (node (ref "JP7") (pin "9") (pinfunction "9_9") (pintype "passive"))
      (node (ref "R16") (pin "2") (pinfunction "2_2") (pintype "passive"))
      (node (ref "U1") (pin "4") (pinfunction "AINN1_4") (pintype "input"))
    )
    (net (code "99") (name "RX_2") (class "Default")
      (node (ref "C20") (pin "1") (pinfunction "1_1") (pintype "passive"))
      (node (ref "JP4") (pin "2") (pinfunction "2_2") (pintype "passive"))
      (node (ref "JP8") (pin "2") (pinfunction "2_2") (pintype "passive"))
    )
    (net (code "100") (name "RX_2_IF+") (class "Default")
      (node (ref "C35") (pin "2") (pinfunction "2_2") (pintype "passive"))
      (node (ref "C51") (pin "2") (pinfunction "2_2") (pintype "passive"))
      (node (ref "IC9") (pin "16") (pinfunction "OUT_D_16") (pintype "bidirectional"))
      (node (ref "JP3") (pin "7") (pinfunction "7_7") (pintype "passive"))
      (node (ref "JP7") (pin "7") (pinfunction "7_7") (pintype "passive"))
      (node (ref "R37") (pin "1") (pinfunction "1_1") (pintype "passive"))
      (node (ref "R38") (pin "1") (pinfunction "1_1") (pintype "passive"))
      (node (ref "U1") (pin "1") (pinfunction "AINP2_1") (pintype "input"))
    )
    (net (code "101") (name "RX_2_IF-") (class "Default")
      (node (ref "C33") (pin "2") (pinfunction "2_2") (pintype "passive"))
      (node (ref "C34") (pin "1") (pinfunction "1_1") (pintype "passive"))
      (node (ref "C36") (pin "1") (pinfunction "1_1") (pintype "passive"))
      (node (ref "C51") (pin "1") (pinfunction "1_1") (pintype "passive"))
      (node (ref "IC9") (pin "10") (pinfunction "OUT_C_10") (pintype "bidirectional"))
      (node (ref "JP3") (pin "5") (pinfunction "5_5") (pintype "passive"))
      (node (ref "JP7") (pin "5") (pinfunction "5_5") (pintype "passive"))
      (node (ref "R36") (pin "2") (pinfunction "2_2") (pintype "passive"))
      (node (ref "U1") (pin "2") (pinfunction "AINN2_2") (pintype "input"))
    )
    (net (code "102") (name "RX_3") (class "Default")
      (node (ref "C24") (pin "1") (pinfunction "1_1") (pintype "passive"))
      (node (ref "JP4") (pin "3") (pinfunction "3_3") (pintype "passive"))
      (node (ref "JP8") (pin "3") (pinfunction "3_3") (pintype "passive"))
    )
    (net (code "103") (name "RX_3_IF+") (class "Default")
      (node (ref "C45") (pin "2") (pinfunction "2_2") (pintype "passive"))
      (node (ref "C52") (pin "2") (pinfunction "2_2") (pintype "passive"))
      (node (ref "IC10") (pin "16") (pinfunction "OUT_D_16") (pintype "bidirectional"))
      (node (ref "JP3") (pin "1") (pinfunction "1_1") (pintype "passive"))
      (node (ref "JP7") (pin "1") (pinfunction "1_1") (pintype "passive"))
      (node (ref "R49") (pin "1") (pinfunction "1_1") (pintype "passive"))
      (node (ref "R50") (pin "1") (pinfunction "1_1") (pintype "passive"))
      (node (ref "U1") (pin "63") (pinfunction "AINP3_63") (pintype "input"))
    )
    (net (code "104") (name "RX_3_IF-") (class "Default")
      (node (ref "C43") (pin "2") (pinfunction "2_2") (pintype "passive"))
      (node (ref "C44") (pin "1") (pinfunction "1_1") (pintype "passive"))
      (node (ref "C46") (pin "1") (pinfunction "1_1") (pintype "passive"))
      (node (ref "C52") (pin "1") (pinfunction "1_1") (pintype "passive"))
      (node (ref "IC10") (pin "10") (pinfunction "OUT_C_10") (pintype "bidirectional"))
      (node (ref "JP3") (pin "3") (pinfunction "3_3") (pintype "passive"))
      (node (ref "JP7") (pin "3") (pinfunction "3_3") (pintype "passive"))
      (node (ref "R48") (pin "2") (pinfunction "2_2") (pintype "passive"))
      (node (ref "U1") (pin "64") (pinfunction "AINN3_64") (pintype "input"))
    )
    (net (code "105") (name "SCLK") (class "Default")
      (node (ref "R66") (pin "2") (pinfunction "2_2") (pintype "passive"))
      (node (ref "U1") (pin "28") (pinfunction "SCLK_28") (pintype "input"))
    )
    (net (code "106") (name "SYNC_BAR") (class "Default")
      (node (ref "R57") (pin "1") (pinfunction "1_1") (pintype "passive"))
      (node (ref "U1") (pin "11") (pinfunction "~{SYNC}_11") (pintype "input"))
    )
    (net (code "107") (name "TEST0") (class "Default")
      (node (ref "R59") (pin "1") (pinfunction "1_1") (pintype "passive"))
      (node (ref "U1") (pin "8") (pinfunction "TEST0_8") (pintype "input"))
    )
    (net (code "108") (name "TEST1") (class "Default")
      (node (ref "R58") (pin "1") (pinfunction "1_1") (pintype "passive"))
      (node (ref "U1") (pin "9") (pinfunction "TEST1_9") (pintype "input"))
    )
    (net (code "109") (name "VG") (class "Default")
      (node (ref "C13") (pin "2") (pinfunction "2_2") (pintype "passive"))
      (node (ref "C29") (pin "2") (pinfunction "2_2") (pintype "passive"))
      (node (ref "C31") (pin "2") (pinfunction "2_2") (pintype "passive"))
      (node (ref "C36") (pin "2") (pinfunction "2_2") (pintype "passive"))
      (node (ref "C39") (pin "2") (pinfunction "2_2") (pintype "passive"))
      (node (ref "C41") (pin "2") (pinfunction "2_2") (pintype "passive"))
      (node (ref "C46") (pin "2") (pinfunction "2_2") (pintype "passive"))
      (node (ref "C6") (pin "2") (pinfunction "2_2") (pintype "passive"))
      (node (ref "C8") (pin "2") (pinfunction "2_2") (pintype "passive"))
      (node (ref "IC10") (pin "14") (pinfunction "+IN_D_14") (pintype "bidirectional"))
      (node (ref "IC3") (pin "14") (pinfunction "+IN_D_14") (pintype "bidirectional"))
      (node (ref "IC4") (pin "1") (pinfunction "OUTPUT_1") (pintype "output"))
      (node (ref "IC9") (pin "14") (pinfunction "+IN_D_14") (pintype "bidirectional"))
      (node (ref "R1") (pin "2") (pinfunction "2_2") (pintype "passive"))
      (node (ref "R11") (pin "1") (pinfunction "1_1") (pintype "passive"))
      (node (ref "R12") (pin "1") (pinfunction "1_1") (pintype "passive"))
      (node (ref "R13") (pin "2") (pinfunction "2_2") (pintype "passive"))
      (node (ref "R14") (pin "1") (pinfunction "1_1") (pintype "passive"))
      (node (ref "R19") (pin "2") (pinfunction "2_2") (pintype "passive"))
      (node (ref "R20") (pin "2") (pinfunction "2_2") (pintype "passive"))
      (node (ref "R22") (pin "2") (pinfunction "2_2") (pintype "passive"))
      (node (ref "R23") (pin "2") (pinfunction "2_2") (pintype "passive"))
      (node (ref "R24") (pin "2") (pinfunction "2_2") (pintype "passive"))
      (node (ref "R26") (pin "2") (pinfunction "2_2") (pintype "passive"))
      (node (ref "R27") (pin "2") (pinfunction "2_2") (pintype "passive"))
      (node (ref "R3") (pin "2") (pinfunction "2_2") (pintype "passive"))
      (node (ref "R30") (pin "1") (pinfunction "1_1") (pintype "passive"))
      (node (ref "R33") (pin "1") (pinfunction "1_1") (pintype "passive"))
      (node (ref "R34") (pin "1") (pinfunction "1_1") (pintype "passive"))
      (node (ref "R39") (pin "2") (pinfunction "2_2") (pintype "passive"))
      (node (ref "R42") (pin "1") (pinfunction "1_1") (pintype "passive"))
      (node (ref "R45") (pin "1") (pinfunction "1_1") (pintype "passive"))
      (node (ref "R46") (pin "1") (pinfunction "1_1") (pintype "passive"))
      (node (ref "R51") (pin "2") (pinfunction "2_2") (pintype "passive"))
      (node (ref "R6") (pin "1") (pinfunction "1_1") (pintype "passive"))
    )
    (net (code "110") (name "VGA_OUT_RX_1") (class "Default")
      (node (ref "IC1") (pin "1") (pinfunction "OUT_1") (pintype "output"))
      (node (ref "R2") (pin "2") (pinfunction "2_2") (pintype "passive"))
      (node (ref "R4") (pin "1") (pinfunction "1_1") (pintype "passive"))
    )
    (net (code "111") (name "VGA_OUT_RX_2") (class "Default")
      (node (ref "IC6") (pin "1") (pinfunction "OUT_1") (pintype "output"))
      (node (ref "R21") (pin "2") (pinfunction "2_2") (pintype "passive"))
      (node (ref "R28") (pin "1") (pinfunction "1_1") (pintype "passive"))
    )
    (net (code "112") (name "VGA_OUT_RX_3") (class "Default")
      (node (ref "IC8") (pin "1") (pinfunction "OUT_1") (pintype "output"))
      (node (ref "R25") (pin "2") (pinfunction "2_2") (pintype "passive"))
      (node (ref "R40") (pin "1") (pinfunction "1_1") (pintype "passive"))
    )
    (net (code "113") (name "unconnected-(IC3-NC_1-Pad8)") (class "Default")
      (node (ref "IC3") (pin "8") (pinfunction "NC_1_8") (pintype "bidirectional"))
    )
    (net (code "114") (name "unconnected-(IC3-NC_2-Pad9)") (class "Default")
      (node (ref "IC3") (pin "9") (pinfunction "NC_2_9") (pintype "bidirectional"))
    )
    (net (code "115") (name "unconnected-(IC9-NC_1-Pad8)") (class "Default")
      (node (ref "IC9") (pin "8") (pinfunction "NC_1_8") (pintype "bidirectional"))
    )
    (net (code "116") (name "unconnected-(IC9-NC_2-Pad9)") (class "Default")
      (node (ref "IC9") (pin "9") (pinfunction "NC_2_9") (pintype "bidirectional"))
    )
    (net (code "117") (name "unconnected-(IC10-NC_1-Pad8)") (class "Default")
      (node (ref "IC10") (pin "8") (pinfunction "NC_1_8") (pintype "bidirectional"))
    )
    (net (code "118") (name "unconnected-(IC10-NC_2-Pad9)") (class "Default")
      (node (ref "IC10") (pin "9") (pinfunction "NC_2_9") (pintype "bidirectional"))
    )
    (net (code "119") (name "unconnected-(IC11-NC-Pad5)") (class "Default")
      (node (ref "IC11") (pin "5") (pinfunction "NC_5") (pintype "no_connect"))
    )
    (net (code "120") (name "unconnected-(IC12-NC-Pad4)") (class "Default")
      (node (ref "IC12") (pin "4") (pinfunction "NC_4") (pintype "no_connect"))
    )
    (net (code "121") (name "unconnected-(U1-AINN4-Pad62)") (class "Default")
      (node (ref "U1") (pin "62") (pinfunction "AINN4_62") (pintype "input"))
    )
    (net (code "122") (name "unconnected-(U1-AINN5-Pad52)") (class "Default")
      (node (ref "U1") (pin "52") (pinfunction "AINN5_52") (pintype "no_connect"))
    )
    (net (code "123") (name "unconnected-(U1-AINN6-Pad50)") (class "Default")
      (node (ref "U1") (pin "50") (pinfunction "AINN6_50") (pintype "no_connect"))
    )
    (net (code "124") (name "unconnected-(U1-AINN7-Pad48)") (class "Default")
      (node (ref "U1") (pin "48") (pinfunction "AINN7_48") (pintype "no_connect"))
    )
    (net (code "125") (name "unconnected-(U1-AINN8-Pad46)") (class "Default")
      (node (ref "U1") (pin "46") (pinfunction "AINN8_46") (pintype "no_connect"))
    )
    (net (code "126") (name "unconnected-(U1-AINP4-Pad61)") (class "Default")
      (node (ref "U1") (pin "61") (pinfunction "AINP4_61") (pintype "input"))
    )
    (net (code "127") (name "unconnected-(U1-AINP5-Pad51)") (class "Default")
      (node (ref "U1") (pin "51") (pinfunction "AINP5_51") (pintype "no_connect"))
    )
    (net (code "128") (name "unconnected-(U1-AINP6-Pad49)") (class "Default")
      (node (ref "U1") (pin "49") (pinfunction "AINP6_49") (pintype "no_connect"))
    )
    (net (code "129") (name "unconnected-(U1-AINP7-Pad47)") (class "Default")
      (node (ref "U1") (pin "47") (pinfunction "AINP7_47") (pintype "no_connect"))
    )
    (net (code "130") (name "unconnected-(U1-AINP8-Pad45)") (class "Default")
      (node (ref "U1") (pin "45") (pinfunction "AINP8_45") (pintype "no_connect"))
    )
    (net (code "131") (name "unconnected-(U1-DOUT5-Pad16)") (class "Default")
      (node (ref "U1") (pin "16") (pinfunction "DOUT5_16") (pintype "output"))
    )
    (net (code "132") (name "unconnected-(U1-DOUT6-Pad15)") (class "Default")
      (node (ref "U1") (pin "15") (pinfunction "DOUT6_15") (pintype "output"))
    )
    (net (code "133") (name "unconnected-(U1-DOUT7-Pad14)") (class "Default")
      (node (ref "U1") (pin "14") (pinfunction "DOUT7_14") (pintype "output"))
    )
    (net (code "134") (name "unconnected-(U1-DOUT8-Pad13)") (class "Default")
      (node (ref "U1") (pin "13") (pinfunction "DOUT8_13") (pintype "output"))
    )
    (net (code "135") (name "unconnected-(U1-VCOM-Pad55)") (class "Default")
      (node (ref "U1") (pin "55") (pinfunction "VCOM_55") (pintype "output"))
    )
  )
)
